# HU_revC.net
KiCad netlist of a schematic drawn in Altium Designer
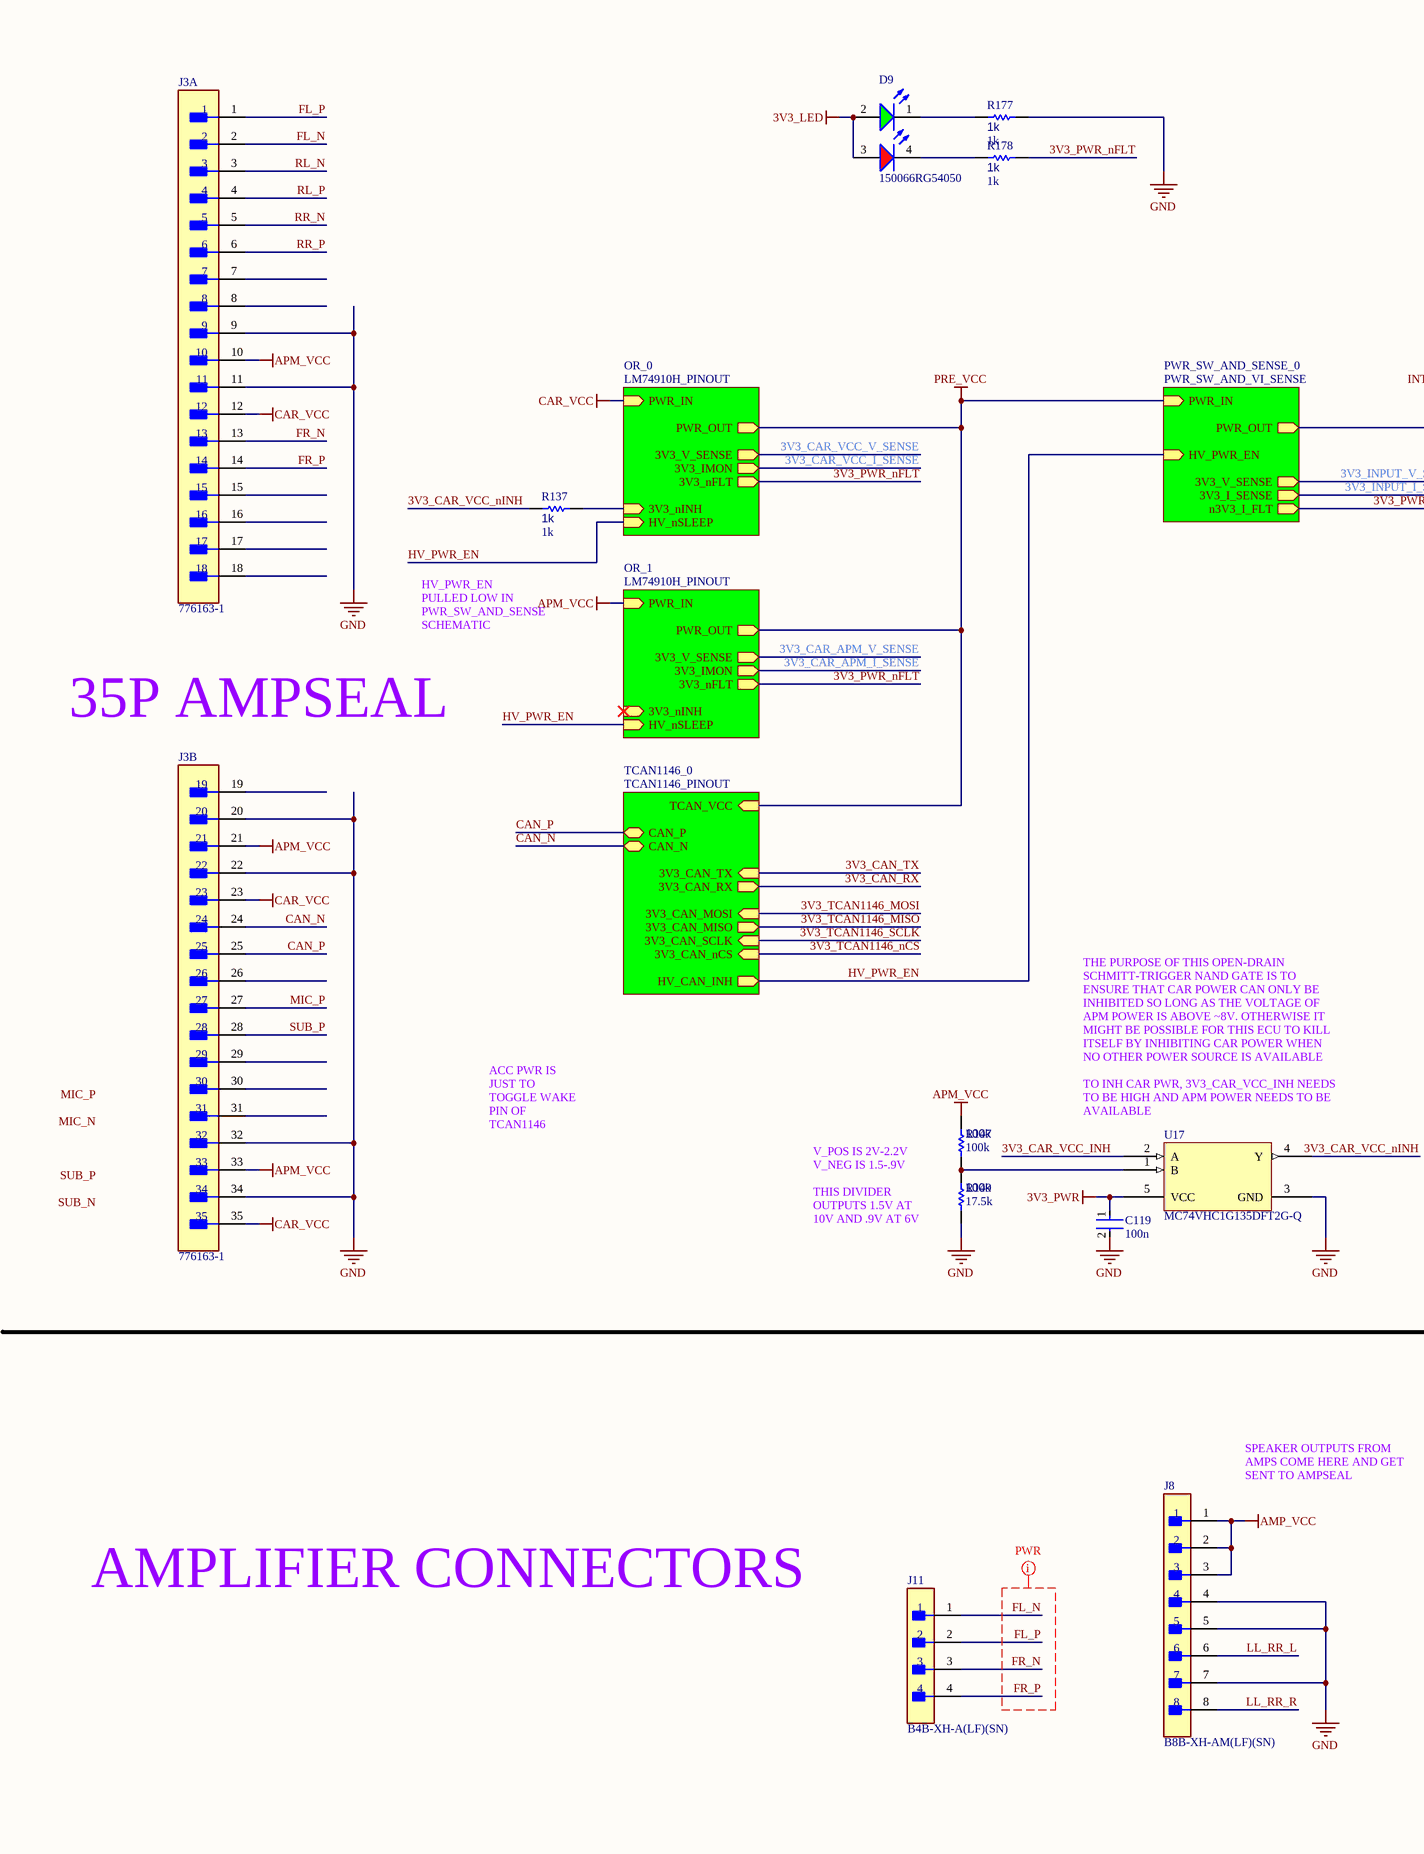
[diagram p0: HU_revC.SchDoc, top left]
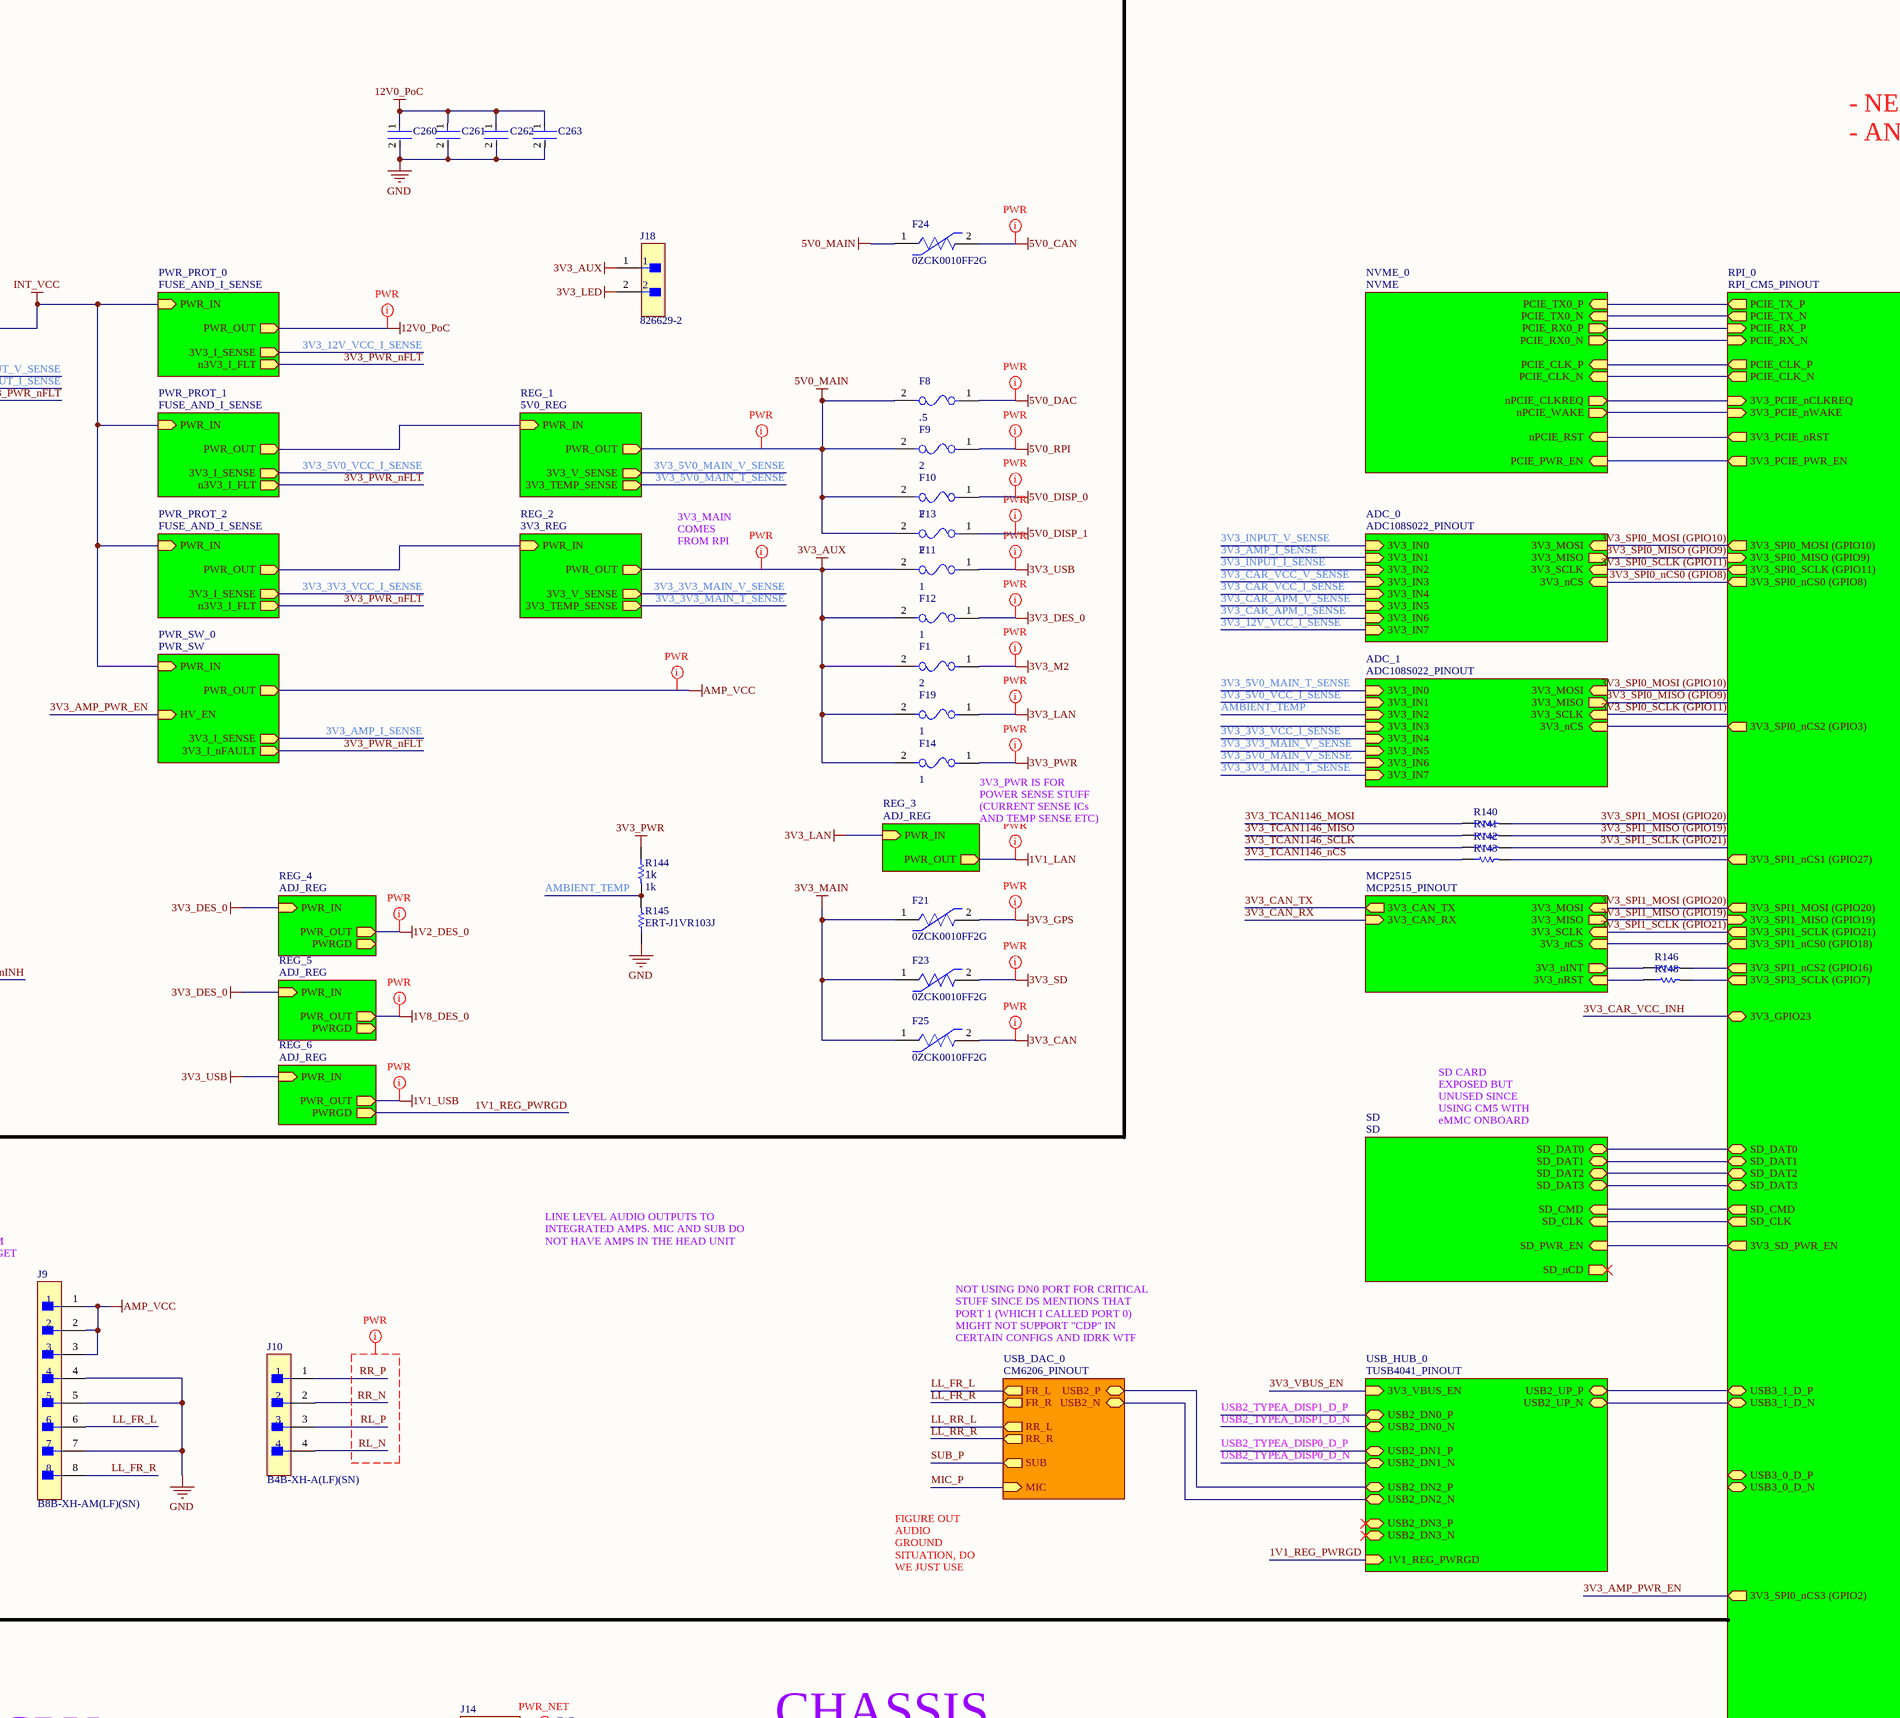
[diagram p1: HU_revC.SchDoc, top middle]
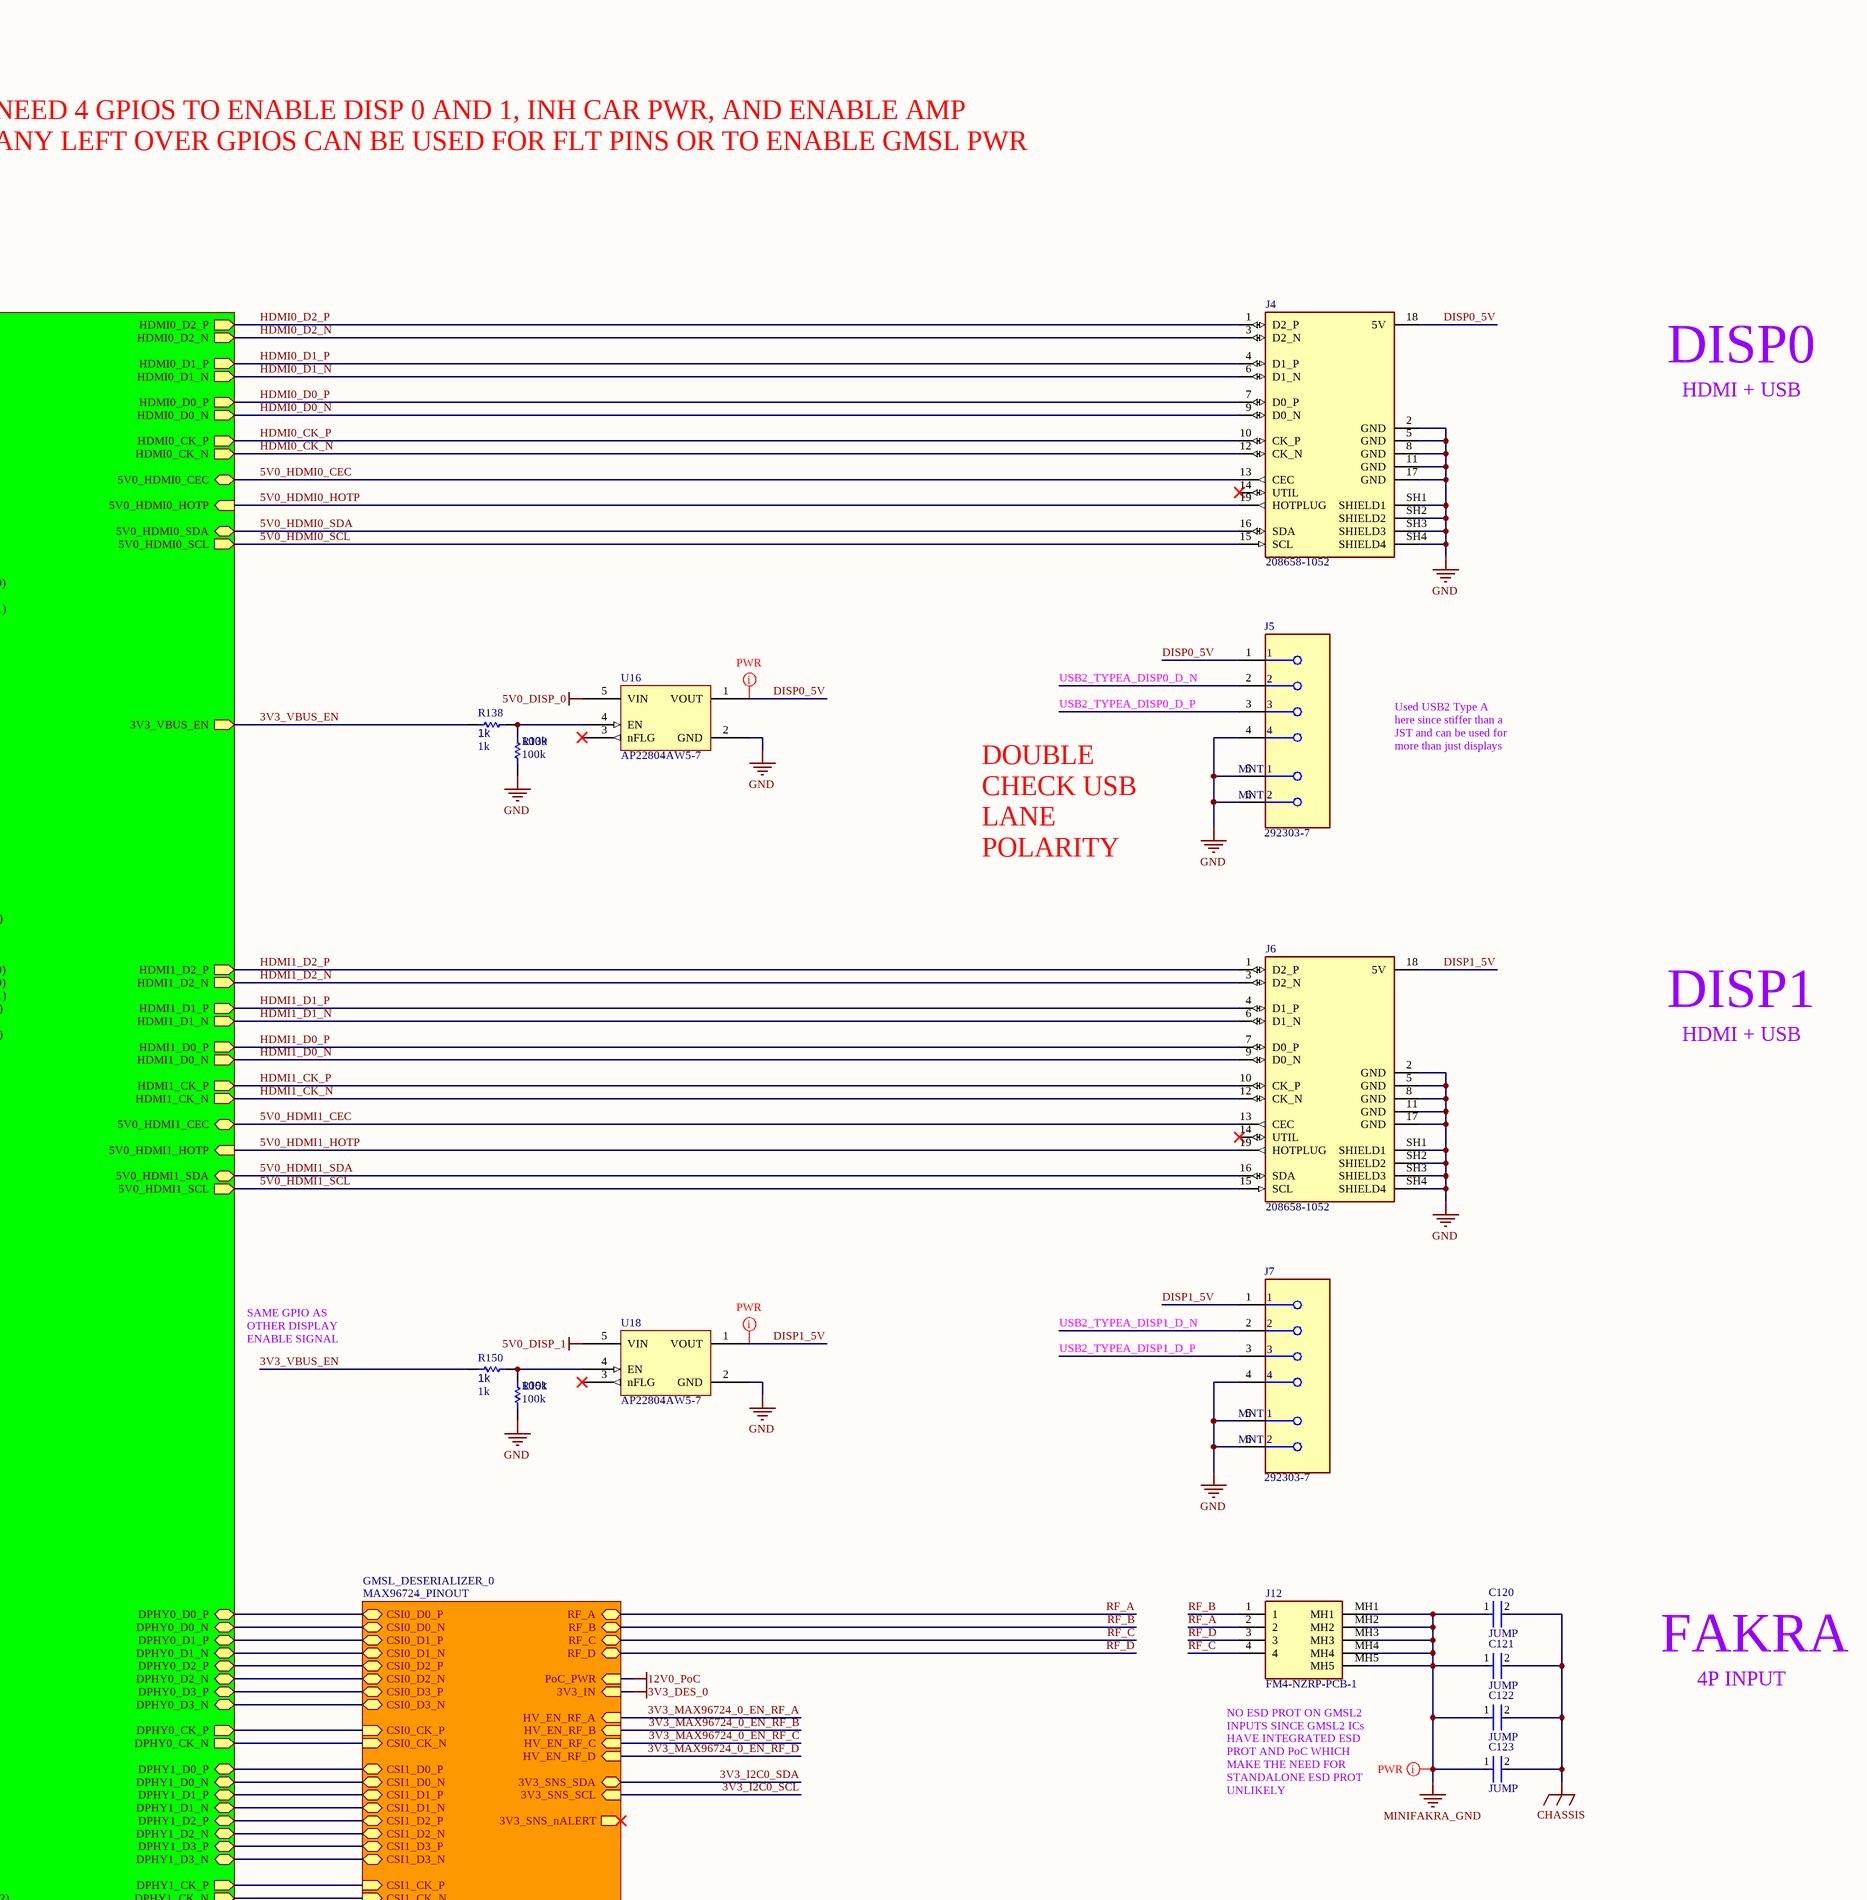
[diagram p2: HU_revC.SchDoc, top right]
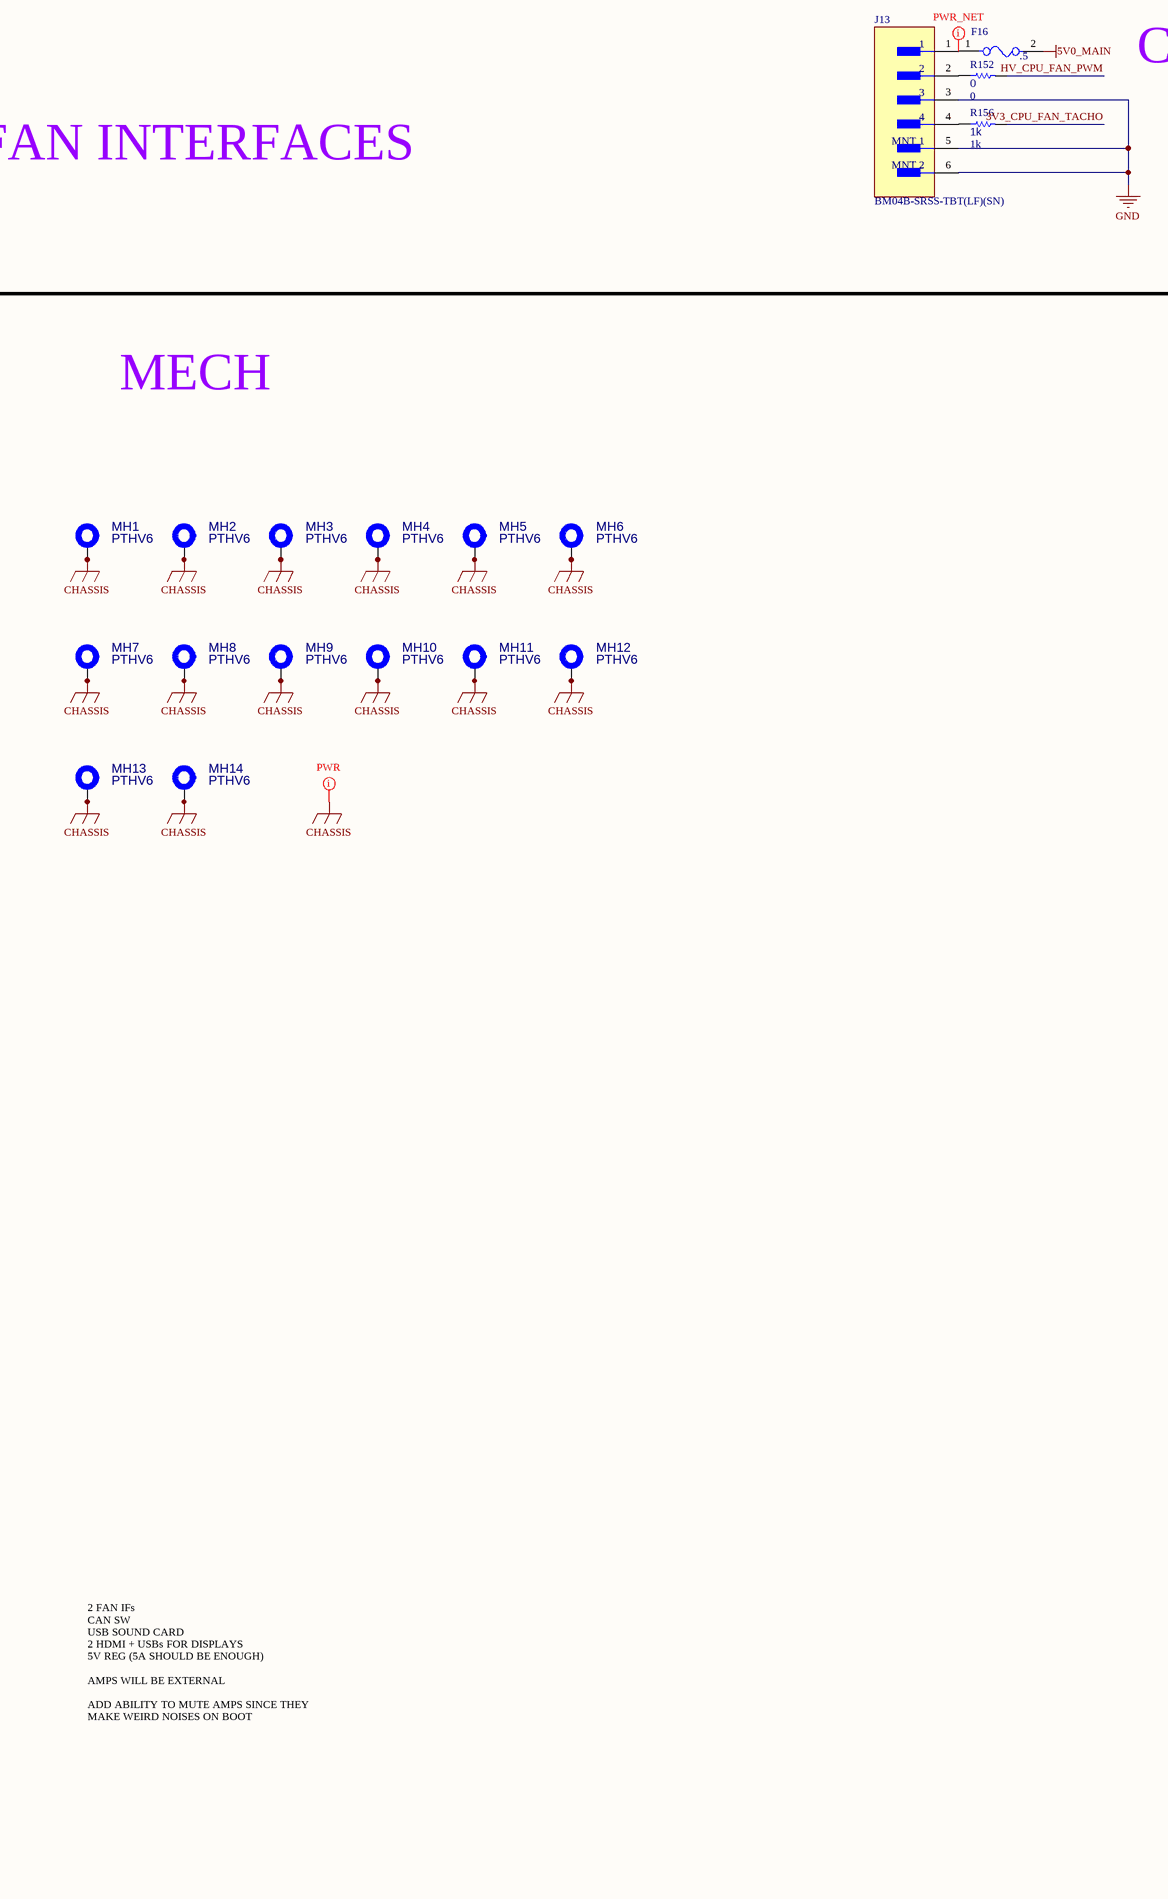
[diagram p3: HU_revC.SchDoc, bottom left]
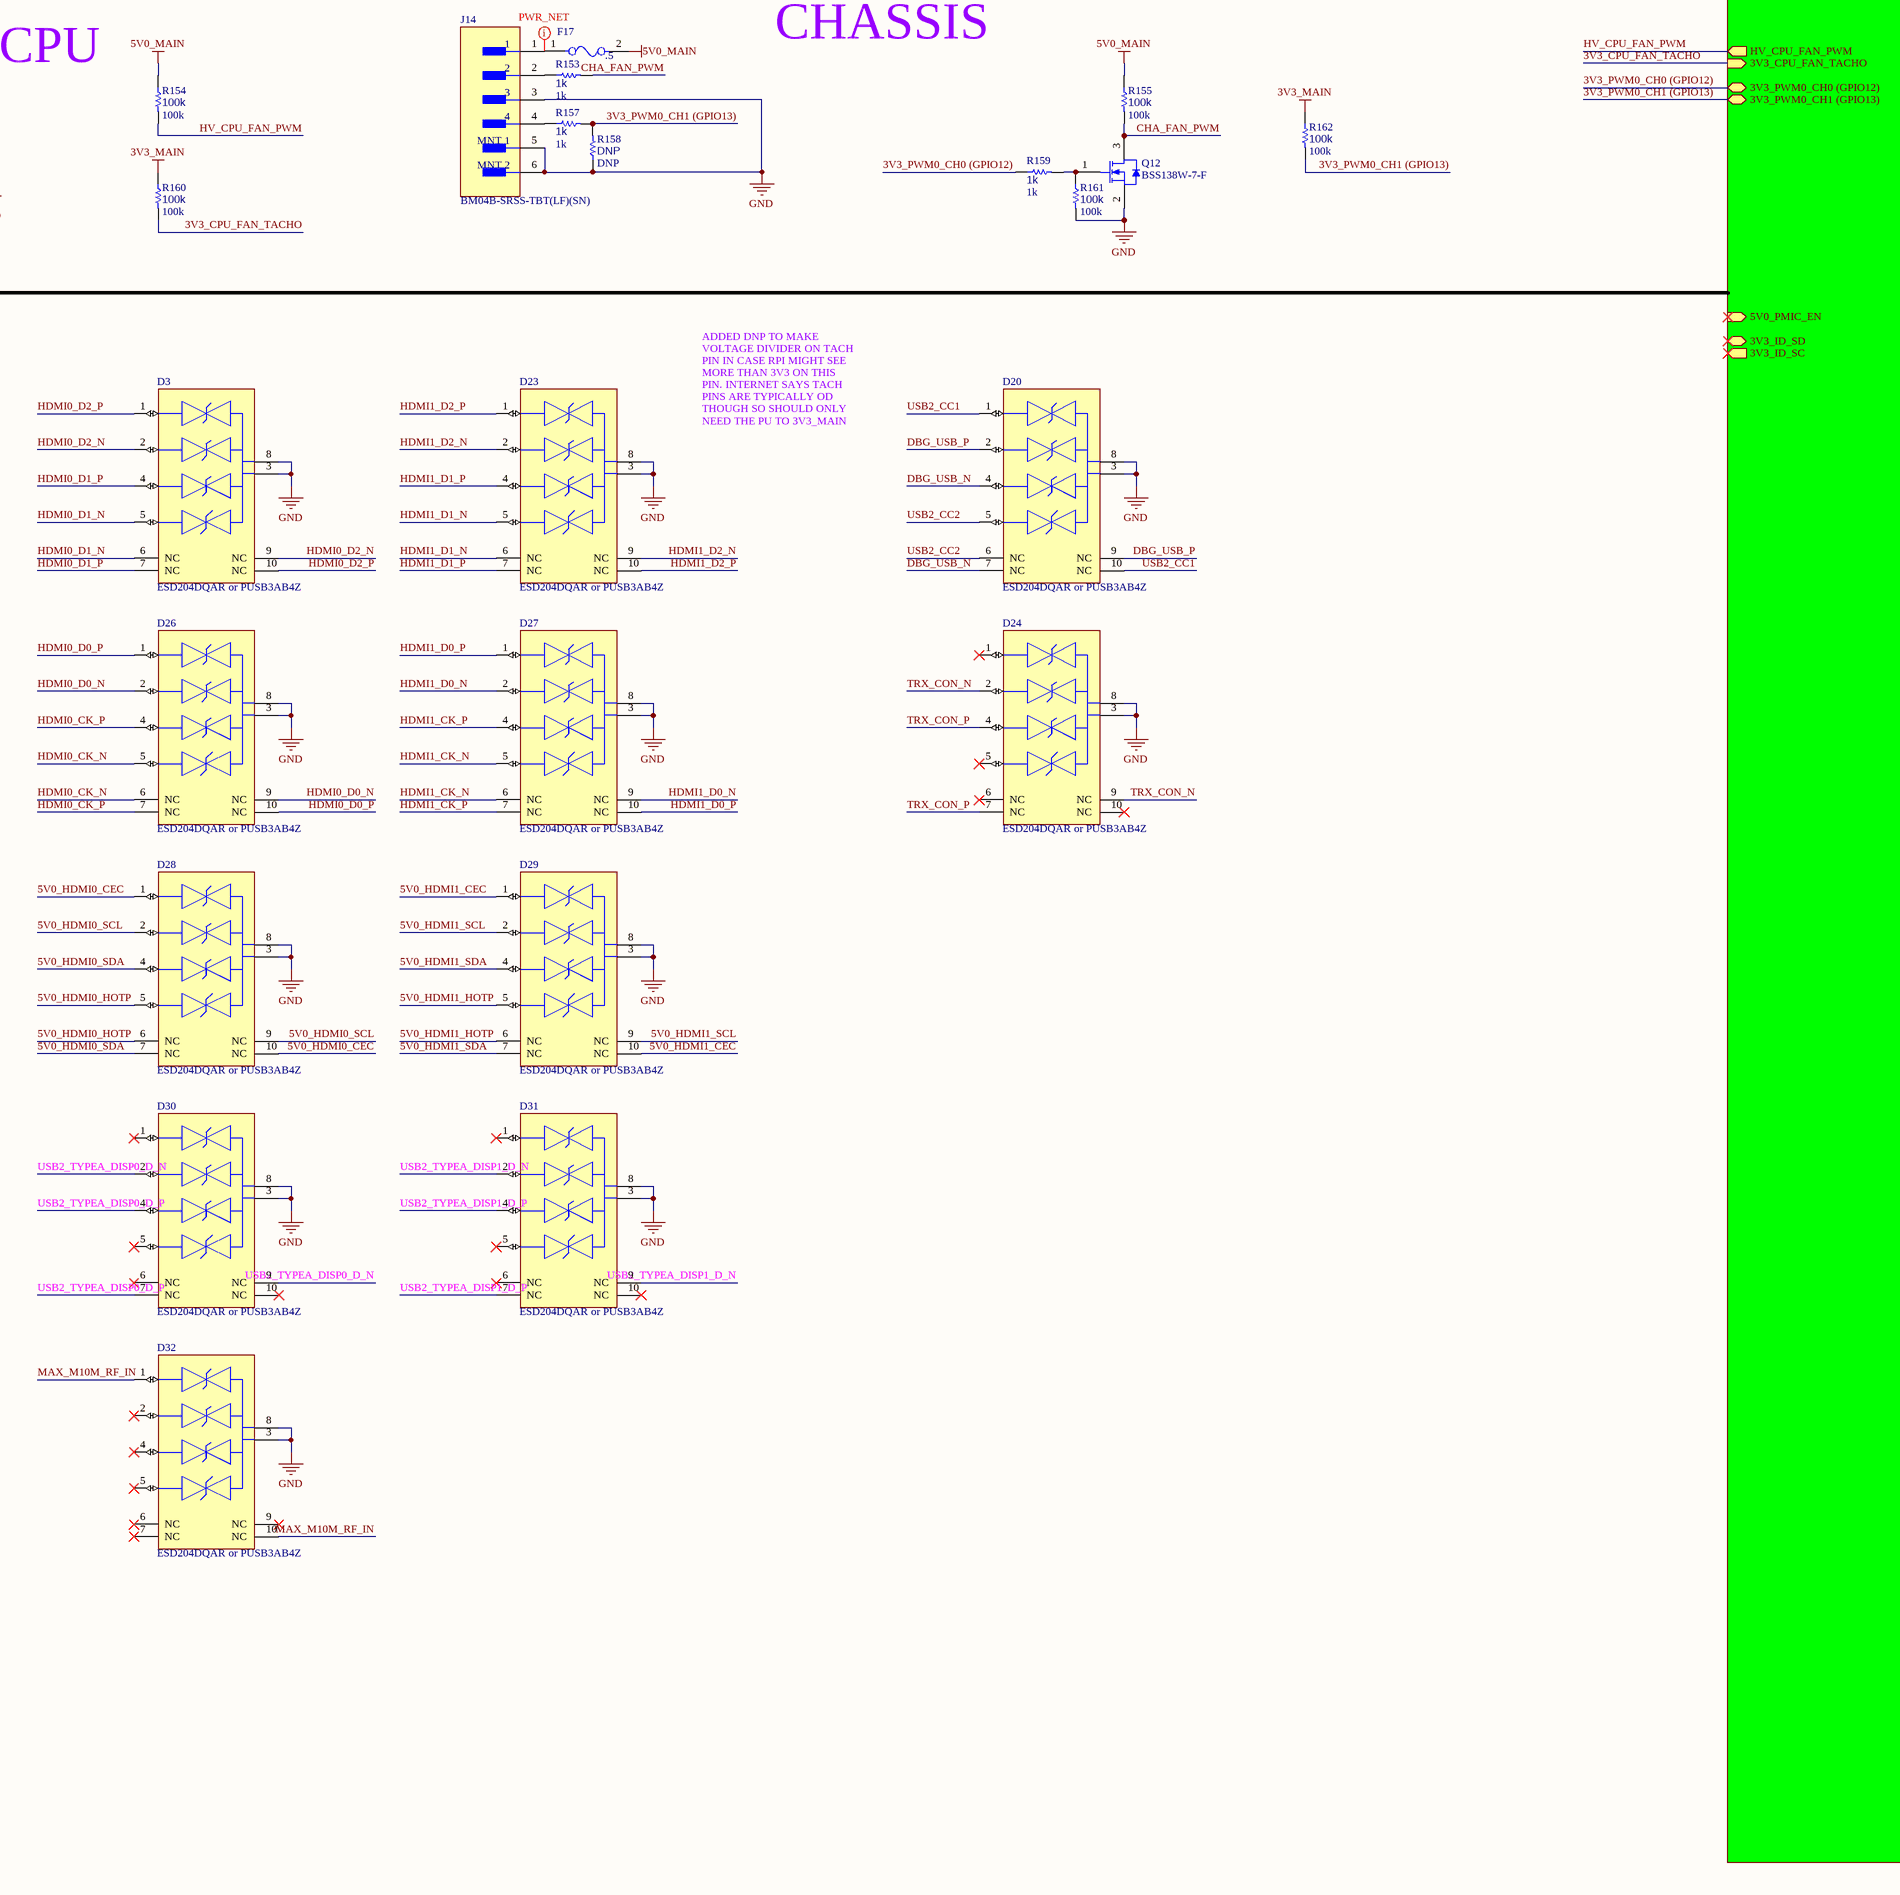
[diagram p4: HU_revC.SchDoc, bottom middle]
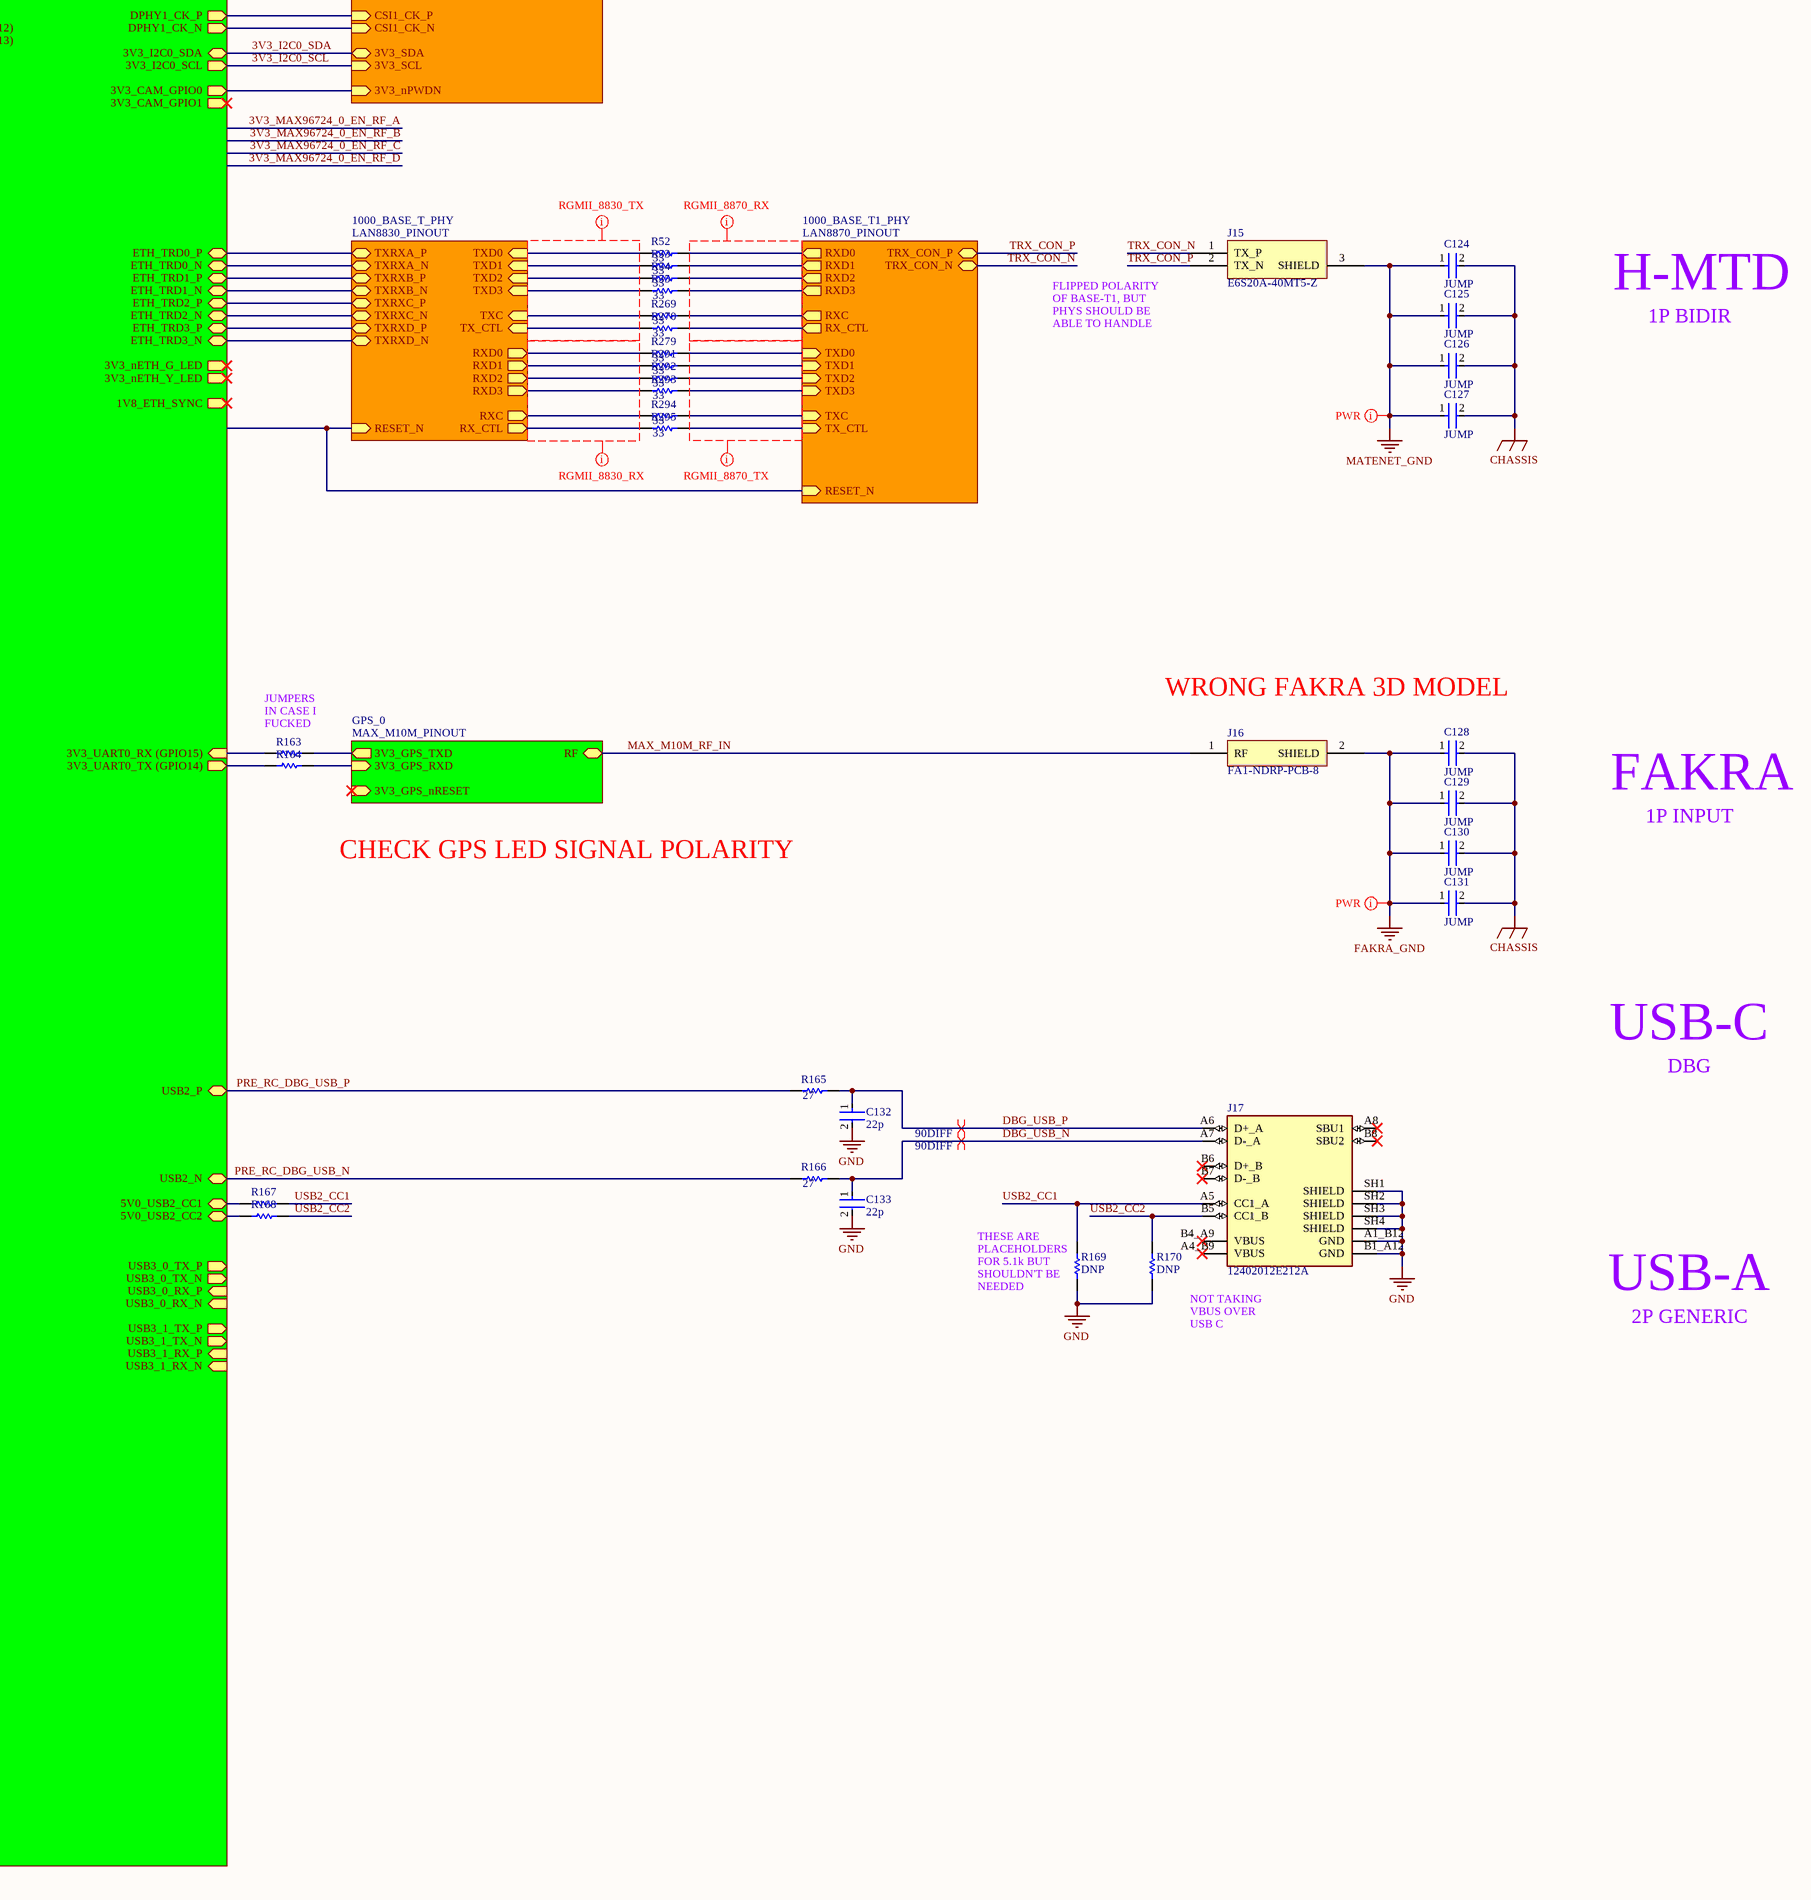
[diagram p5: HU_revC.SchDoc, bottom right]

(export (version "E")
  (design (tool "Eeschema 10.0.6"))
  (components
    (comp (ref "C119")
      (value "100n")
      (footprint "FP-0402-L_1_0_0_05-W_0_5-IPC_A")
      (description "LARGE PADS, 0402 CAP, CHANGE COMMENT TO MATCH REAL P/N")
      (libsource (lib "Space Concordia") (part "b4654b650e69147ec39a6b967a45e02"))
    )
    (comp (ref "C120")
      (value "JUMP")
      (footprint "FP-0402-L_1_0_0_05-W_0_5-IPC_A")
      (description "LARGE PADS, 0402 CAP, CHANGE COMMENT TO MATCH REAL P/N")
      (libsource (lib "Space Concordia") (part "b4654b650e69147ec39a6b967a45e02"))
    )
    (comp (ref "C121")
      (value "JUMP")
      (footprint "FP-0402-L_1_0_0_05-W_0_5-IPC_A")
      (description "LARGE PADS, 0402 CAP, CHANGE COMMENT TO MATCH REAL P/N")
      (libsource (lib "Space Concordia") (part "b4654b650e69147ec39a6b967a45e02"))
    )
    (comp (ref "C122")
      (value "JUMP")
      (footprint "FP-0402-L_1_0_0_05-W_0_5-IPC_A")
      (description "LARGE PADS, 0402 CAP, CHANGE COMMENT TO MATCH REAL P/N")
      (libsource (lib "Space Concordia") (part "b4654b650e69147ec39a6b967a45e02"))
    )
    (comp (ref "C123")
      (value "JUMP")
      (footprint "FP-0402-L_1_0_0_05-W_0_5-IPC_A")
      (description "LARGE PADS, 0402 CAP, CHANGE COMMENT TO MATCH REAL P/N")
      (libsource (lib "Space Concordia") (part "b4654b650e69147ec39a6b967a45e02"))
    )
    (comp (ref "C124")
      (value "JUMP")
      (footprint "FP-0402-L_1_0_0_05-W_0_5-IPC_A")
      (description "LARGE PADS, 0402 CAP, CHANGE COMMENT TO MATCH REAL P/N")
      (libsource (lib "Space Concordia") (part "b4654b650e69147ec39a6b967a45e02"))
    )
    (comp (ref "C125")
      (value "JUMP")
      (footprint "FP-0402-L_1_0_0_05-W_0_5-IPC_A")
      (description "LARGE PADS, 0402 CAP, CHANGE COMMENT TO MATCH REAL P/N")
      (libsource (lib "Space Concordia") (part "b4654b650e69147ec39a6b967a45e02"))
    )
    (comp (ref "C126")
      (value "JUMP")
      (footprint "FP-0402-L_1_0_0_05-W_0_5-IPC_A")
      (description "LARGE PADS, 0402 CAP, CHANGE COMMENT TO MATCH REAL P/N")
      (libsource (lib "Space Concordia") (part "b4654b650e69147ec39a6b967a45e02"))
    )
    (comp (ref "C127")
      (value "JUMP")
      (footprint "FP-0402-L_1_0_0_05-W_0_5-IPC_A")
      (description "LARGE PADS, 0402 CAP, CHANGE COMMENT TO MATCH REAL P/N")
      (libsource (lib "Space Concordia") (part "b4654b650e69147ec39a6b967a45e02"))
    )
    (comp (ref "C128")
      (value "JUMP")
      (footprint "FP-0402-L_1_0_0_05-W_0_5-IPC_A")
      (description "LARGE PADS, 0402 CAP, CHANGE COMMENT TO MATCH REAL P/N")
      (libsource (lib "Space Concordia") (part "b4654b650e69147ec39a6b967a45e02"))
    )
    (comp (ref "C129")
      (value "JUMP")
      (footprint "FP-0402-L_1_0_0_05-W_0_5-IPC_A")
      (description "LARGE PADS, 0402 CAP, CHANGE COMMENT TO MATCH REAL P/N")
      (libsource (lib "Space Concordia") (part "b4654b650e69147ec39a6b967a45e02"))
    )
    (comp (ref "C130")
      (value "JUMP")
      (footprint "FP-0402-L_1_0_0_05-W_0_5-IPC_A")
      (description "LARGE PADS, 0402 CAP, CHANGE COMMENT TO MATCH REAL P/N")
      (libsource (lib "Space Concordia") (part "b4654b650e69147ec39a6b967a45e02"))
    )
    (comp (ref "C131")
      (value "JUMP")
      (footprint "FP-0402-L_1_0_0_05-W_0_5-IPC_A")
      (description "LARGE PADS, 0402 CAP, CHANGE COMMENT TO MATCH REAL P/N")
      (libsource (lib "Space Concordia") (part "b4654b650e69147ec39a6b967a45e02"))
    )
    (comp (ref "C132")
      (value "22p")
      (footprint "FP-0402-L_1_0_0_05-W_0_5-IPC_A")
      (description "LARGE PADS, 0402 CAP, CHANGE COMMENT TO MATCH REAL P/N")
      (libsource (lib "Space Concordia") (part "b4654b650e69147ec39a6b967a45e02"))
    )
    (comp (ref "C133")
      (value "22p")
      (footprint "FP-0402-L_1_0_0_05-W_0_5-IPC_A")
      (description "LARGE PADS, 0402 CAP, CHANGE COMMENT TO MATCH REAL P/N")
      (libsource (lib "Space Concordia") (part "b4654b650e69147ec39a6b967a45e02"))
    )
    (comp (ref "C260")
      (value "GRM32ER61C476KE15L")
      (footprint "FP-GRM32E-0_3-0_2-IPC_C")
      (description "CAP CER 47UF 16V X5R 1210")
      (fields (field (name "VOLTAGE") "16V") (field (name "TOLERANCE") "10%"))
      (libsource (lib "Altium Content Vault") (part "b4654b650e69147ec39a6b967a45e02"))
    )
    (comp (ref "C261")
      (value "GRM32ER61C476KE15L")
      (footprint "FP-GRM32E-0_3-0_2-IPC_C")
      (description "CAP CER 47UF 16V X5R 1210")
      (fields (field (name "VOLTAGE") "16V") (field (name "TOLERANCE") "10%"))
      (libsource (lib "Altium Content Vault") (part "b4654b650e69147ec39a6b967a45e02"))
    )
    (comp (ref "C262")
      (value "GRM32ER61C476KE15L")
      (footprint "FP-GRM32E-0_3-0_2-IPC_C")
      (description "CAP CER 47UF 16V X5R 1210")
      (fields (field (name "VOLTAGE") "16V") (field (name "TOLERANCE") "10%"))
      (libsource (lib "Altium Content Vault") (part "b4654b650e69147ec39a6b967a45e02"))
    )
    (comp (ref "C263")
      (value "GRM32ER61C476KE15L")
      (footprint "FP-GRM32E-0_3-0_2-IPC_C")
      (description "CAP CER 47UF 16V X5R 1210")
      (fields (field (name "VOLTAGE") "16V") (field (name "TOLERANCE") "10%"))
      (libsource (lib "Altium Content Vault") (part "b4654b650e69147ec39a6b967a45e02"))
    )
    (comp (ref "D3")
      (value "ESD204DQAR or PUSB3AB4Z")
      (footprint "FP-DQA0010A-MFG")
      (description "4-CHANNEL LOW-CAPACITANCE SURGE")
      (fields
        (field (name "MANUFACTURER") "Texas Instruments")
        (field (name "OCTOPART") "https://octopart.com/esd204dqar-texas+instruments-89917476")
      )
      (libsource (lib "Altium Content Vault") (part "1465e58c1818c7767b55926832f0bf5"))
    )
    (comp (ref "D9")
      (value "150066RG54050")
      (footprint "WL-SBCD_0606")
      (description "Led, Red/Grn, 180Mcd/230Mcd, 624Nm/525Nm Rohs Compliant: Yes")
      (fields (field (name "SOURCE") "rgled.SchLib"))
      (libsource (lib "Space Concordia") (part "CMP-004-00034-2"))
    )
    (comp (ref "D20")
      (value "ESD204DQAR or PUSB3AB4Z")
      (footprint "FP-DQA0010A-MFG")
      (description "4-CHANNEL LOW-CAPACITANCE SURGE")
      (fields
        (field (name "MANUFACTURER") "Texas Instruments")
        (field (name "OCTOPART") "https://octopart.com/esd204dqar-texas+instruments-89917476")
      )
      (libsource (lib "Altium Content Vault") (part "1465e58c1818c7767b55926832f0bf5"))
    )
    (comp (ref "D23")
      (value "ESD204DQAR or PUSB3AB4Z")
      (footprint "FP-DQA0010A-MFG")
      (description "4-CHANNEL LOW-CAPACITANCE SURGE")
      (fields
        (field (name "MANUFACTURER") "Texas Instruments")
        (field (name "OCTOPART") "https://octopart.com/esd204dqar-texas+instruments-89917476")
      )
      (libsource (lib "Altium Content Vault") (part "1465e58c1818c7767b55926832f0bf5"))
    )
    (comp (ref "D24")
      (value "ESD204DQAR or PUSB3AB4Z")
      (footprint "FP-DQA0010A-MFG")
      (description "4-CHANNEL LOW-CAPACITANCE SURGE")
      (fields
        (field (name "MANUFACTURER") "Texas Instruments")
        (field (name "OCTOPART") "https://octopart.com/esd204dqar-texas+instruments-89917476")
      )
      (libsource (lib "Altium Content Vault") (part "1465e58c1818c7767b55926832f0bf5"))
    )
    (comp (ref "D26")
      (value "ESD204DQAR or PUSB3AB4Z")
      (footprint "FP-DQA0010A-MFG")
      (description "4-CHANNEL LOW-CAPACITANCE SURGE")
      (fields
        (field (name "MANUFACTURER") "Texas Instruments")
        (field (name "OCTOPART") "https://octopart.com/esd204dqar-texas+instruments-89917476")
      )
      (libsource (lib "Altium Content Vault") (part "1465e58c1818c7767b55926832f0bf5"))
    )
    (comp (ref "D27")
      (value "ESD204DQAR or PUSB3AB4Z")
      (footprint "FP-DQA0010A-MFG")
      (description "4-CHANNEL LOW-CAPACITANCE SURGE")
      (fields
        (field (name "MANUFACTURER") "Texas Instruments")
        (field (name "OCTOPART") "https://octopart.com/esd204dqar-texas+instruments-89917476")
      )
      (libsource (lib "Altium Content Vault") (part "1465e58c1818c7767b55926832f0bf5"))
    )
    (comp (ref "D28")
      (value "ESD204DQAR or PUSB3AB4Z")
      (footprint "FP-DQA0010A-MFG")
      (description "4-CHANNEL LOW-CAPACITANCE SURGE")
      (fields
        (field (name "MANUFACTURER") "Texas Instruments")
        (field (name "OCTOPART") "https://octopart.com/esd204dqar-texas+instruments-89917476")
      )
      (libsource (lib "Altium Content Vault") (part "1465e58c1818c7767b55926832f0bf5"))
    )
    (comp (ref "D29")
      (value "ESD204DQAR or PUSB3AB4Z")
      (footprint "FP-DQA0010A-MFG")
      (description "4-CHANNEL LOW-CAPACITANCE SURGE")
      (fields
        (field (name "MANUFACTURER") "Texas Instruments")
        (field (name "OCTOPART") "https://octopart.com/esd204dqar-texas+instruments-89917476")
      )
      (libsource (lib "Altium Content Vault") (part "1465e58c1818c7767b55926832f0bf5"))
    )
    (comp (ref "D30")
      (value "ESD204DQAR or PUSB3AB4Z")
      (footprint "FP-DQA0010A-MFG")
      (description "4-CHANNEL LOW-CAPACITANCE SURGE")
      (fields
        (field (name "MANUFACTURER") "Texas Instruments")
        (field (name "OCTOPART") "https://octopart.com/esd204dqar-texas+instruments-89917476")
      )
      (libsource (lib "Altium Content Vault") (part "1465e58c1818c7767b55926832f0bf5"))
    )
    (comp (ref "D31")
      (value "ESD204DQAR or PUSB3AB4Z")
      (footprint "FP-DQA0010A-MFG")
      (description "4-CHANNEL LOW-CAPACITANCE SURGE")
      (fields
        (field (name "MANUFACTURER") "Texas Instruments")
        (field (name "OCTOPART") "https://octopart.com/esd204dqar-texas+instruments-89917476")
      )
      (libsource (lib "Altium Content Vault") (part "1465e58c1818c7767b55926832f0bf5"))
    )
    (comp (ref "D32")
      (value "ESD204DQAR or PUSB3AB4Z")
      (footprint "FP-DQA0010A-MFG")
      (description "4-CHANNEL LOW-CAPACITANCE SURGE")
      (fields
        (field (name "MANUFACTURER") "Texas Instruments")
        (field (name "OCTOPART") "https://octopart.com/esd204dqar-texas+instruments-89917476")
      )
      (libsource (lib "Altium Content Vault") (part "1465e58c1818c7767b55926832f0bf5"))
    )
    (comp (ref "F1")
      (value "2")
      (footprint "FP-0685T-MFG")
      (description "FUSE BOARD MNT 5A 63VAC/VDC 1206")
      (libsource (lib "Altium Content Vault") (part "5bcf9b9f640e542cf0359d10258e979"))
    )
    (comp (ref "F8")
      (value ".5")
      (footprint "FP-0685T-MFG")
      (description "FUSE BOARD MNT 5A 63VAC/VDC 1206")
      (libsource (lib "Altium Content Vault") (part "5bcf9b9f640e542cf0359d10258e979"))
    )
    (comp (ref "F9")
      (value "2")
      (footprint "FP-0685T-MFG")
      (description "FUSE BOARD MNT 5A 63VAC/VDC 1206")
      (libsource (lib "Altium Content Vault") (part "5bcf9b9f640e542cf0359d10258e979"))
    )
    (comp (ref "F10")
      (value "2")
      (footprint "FP-0685T-MFG")
      (description "FUSE BOARD MNT 5A 63VAC/VDC 1206")
      (libsource (lib "Altium Content Vault") (part "5bcf9b9f640e542cf0359d10258e979"))
    )
    (comp (ref "F11")
      (value "1")
      (footprint "FP-0685T-MFG")
      (description "FUSE BOARD MNT 5A 63VAC/VDC 1206")
      (libsource (lib "Altium Content Vault") (part "5bcf9b9f640e542cf0359d10258e979"))
    )
    (comp (ref "F12")
      (value "1")
      (footprint "FP-0685T-MFG")
      (description "FUSE BOARD MNT 5A 63VAC/VDC 1206")
      (libsource (lib "Altium Content Vault") (part "5bcf9b9f640e542cf0359d10258e979"))
    )
    (comp (ref "F13")
      (value "2")
      (footprint "FP-0685T-MFG")
      (description "FUSE BOARD MNT 5A 63VAC/VDC 1206")
      (libsource (lib "Altium Content Vault") (part "5bcf9b9f640e542cf0359d10258e979"))
    )
    (comp (ref "F14")
      (value "1")
      (footprint "FP-0685T-MFG")
      (description "FUSE BOARD MNT 5A 63VAC/VDC 1206")
      (libsource (lib "Altium Content Vault") (part "5bcf9b9f640e542cf0359d10258e979"))
    )
    (comp (ref "F16")
      (value ".5")
      (footprint "FP-0685T-MFG")
      (description "FUSE BOARD MNT 5A 63VAC/VDC 1206")
      (libsource (lib "Altium Content Vault") (part "5bcf9b9f640e542cf0359d10258e979"))
    )
    (comp (ref "F17")
      (value ".5")
      (footprint "FP-0685T-MFG")
      (description "FUSE BOARD MNT 5A 63VAC/VDC 1206")
      (libsource (lib "Altium Content Vault") (part "5bcf9b9f640e542cf0359d10258e979"))
    )
    (comp (ref "F19")
      (value "1")
      (footprint "FP-0685T-MFG")
      (description "FUSE BOARD MNT 5A 63VAC/VDC 1206")
      (libsource (lib "Altium Content Vault") (part "5bcf9b9f640e542cf0359d10258e979"))
    )
    (comp (ref "F21")
      (value "0ZCK0010FF2G")
      (footprint "FP-0ZCK0010FF2G-MFG")
      (description "PTC RESET FUSE 15V 100MA 0805")
      (libsource (lib "Altium Content Vault") (part "fc31388045fc42ab786d6d00b506e9f"))
    )
    (comp (ref "F23")
      (value "0ZCK0010FF2G")
      (footprint "FP-0ZCK0010FF2G-MFG")
      (description "PTC RESET FUSE 15V 100MA 0805")
      (libsource (lib "Altium Content Vault") (part "fc31388045fc42ab786d6d00b506e9f"))
    )
    (comp (ref "F24")
      (value "0ZCK0010FF2G")
      (footprint "FP-0ZCK0010FF2G-MFG")
      (description "PTC RESET FUSE 15V 100MA 0805")
      (libsource (lib "Altium Content Vault") (part "fc31388045fc42ab786d6d00b506e9f"))
    )
    (comp (ref "F25")
      (value "0ZCK0010FF2G")
      (footprint "FP-0ZCK0010FF2G-MFG")
      (description "PTC RESET FUSE 15V 100MA 0805")
      (libsource (lib "Altium Content Vault") (part "fc31388045fc42ab786d6d00b506e9f"))
    )
    (comp (ref "J3")
      (value "776163-1")
      (footprint "FP-776163-1-MFG")
      (description "CONN HEADER R/A 35POS 4MM")
      (libsource (lib "Altium Content Vault") (part "519b18991870a11d3ebcd8ad3c0113e"))
    )
    (comp (ref "J4")
      (value "208658-1052")
      (footprint "208658-1052-Footprint-1")
      (description "HDMI CONNECTOR, RCPT, 19POS, SMT; Available until stocks are exhausted Alternative available")
      (libsource (lib "Space Concordia") (part "208658-1052"))
    )
    (comp (ref "J5")
      (value "292303-7")
      (footprint "FP-292303-7-MFG")
      (description "CONN RCPT USB2.0 TYPEA 4P SMD RA")
      (fields
        (field (name "OCTOPART") "https://octopart.com/292303-7-te+connectivity-42840369")
        (field (name "MANUFACTURER") "TE Connectivity")
      )
      (libsource (lib "Altium Content Vault") (part "79e6714efa0bb2f851c24b2688127c9"))
    )
    (comp (ref "J6")
      (value "208658-1052")
      (footprint "208658-1052-Footprint-1")
      (description "HDMI CONNECTOR, RCPT, 19POS, SMT; Available until stocks are exhausted Alternative available")
      (libsource (lib "Space Concordia") (part "208658-1052"))
    )
    (comp (ref "J7")
      (value "292303-7")
      (footprint "FP-292303-7-MFG")
      (description "CONN RCPT USB2.0 TYPEA 4P SMD RA")
      (fields
        (field (name "OCTOPART") "https://octopart.com/292303-7-te+connectivity-42840369")
        (field (name "MANUFACTURER") "TE Connectivity")
      )
      (libsource (lib "Altium Content Vault") (part "79e6714efa0bb2f851c24b2688127c9"))
    )
    (comp (ref "J8")
      (value "B8B-XH-AM(LF)(SN)")
      (footprint "FP-B8B-XH-AM_LF_SN-MFG")
      (description "CONN HEADER VERT 8POS 2.5MM")
      (libsource (lib "Altium Content Vault") (part "99ec2b232beb5d2356d4d77f6a047f0"))
    )
    (comp (ref "J9")
      (value "B8B-XH-AM(LF)(SN)")
      (footprint "FP-B8B-XH-AM_LF_SN-MFG")
      (description "CONN HEADER VERT 8POS 2.5MM")
      (libsource (lib "Altium Content Vault") (part "99ec2b232beb5d2356d4d77f6a047f0"))
    )
    (comp (ref "J10")
      (value "B4B-XH-A(LF)(SN)")
      (footprint "FP-B4B-XH-A_LF_SN-MFG")
      (description "CONN HEADER VERT 4POS 2.5MM")
      (libsource (lib "Altium Content Vault") (part "299a8cea1bdcbc3624fe62c390fa72c"))
    )
    (comp (ref "J11")
      (value "B4B-XH-A(LF)(SN)")
      (footprint "FP-B4B-XH-A_LF_SN-MFG")
      (description "CONN HEADER VERT 4POS 2.5MM")
      (libsource (lib "Altium Content Vault") (part "299a8cea1bdcbc3624fe62c390fa72c"))
    )
    (comp (ref "J12")
      (value "FM4-NZRP-PCB-1")
      (footprint "FM4-NZRP-PCB-1-Footprint-1")
      (description "Connector RF Mini-FAKRA Plug 9GHz 50Ohm Solder Right Angle Through Hole")
      (libsource (lib "Space Concordia") (part "CMP-002-00085-1"))
    )
    (comp (ref "J13")
      (value "BM04B-SRSS-TBT(LF)(SN)")
      (footprint "FP-BM04B-SRSS-TBT_LF_SN-MFG")
      (description "CONN HEADER SMD 4POS 1MM")
      (libsource (lib "Altium Content Vault") (part "8e3688c4b118bffc0dd9b7401e414ba"))
    )
    (comp (ref "J14")
      (value "BM04B-SRSS-TBT(LF)(SN)")
      (footprint "FP-BM04B-SRSS-TBT_LF_SN-MFG")
      (description "CONN HEADER SMD 4POS 1MM")
      (libsource (lib "Altium Content Vault") (part "8e3688c4b118bffc0dd9b7401e414ba"))
    )
    (comp (ref "J15")
      (value "E6S20A-40MT5-Z")
      (footprint "E6S20A-40MT5-Z-Footprint-1")
      (description "RF Connector, 2 Contact(s), Male, Panel Mount, Board And Panel Mount, Solder Terminal, Plug")
      (libsource (lib "Space Concordia") (part "E6S20A-40MT5-Z"))
    )
    (comp (ref "J16")
      (value "FA1-NDRP-PCB-8")
      (footprint "FA1-NDRP-PCB-8-Footprint-1")
      (description "RF F Connector, Male, Board Mount, Solder Terminal, Plug")
      (libsource (lib "Space Concordia") (part "FA1-NDRP-PCB-8"))
    )
    (comp (ref "J17")
      (value "12402012E212A")
      (footprint "12402012E212A-Footprint-1")
      (description "USB Connector, USB Type C, USB 2.0, Receptacle, 24 Ways, Surface Mount, Through Hole Mount")
      (libsource (lib "Space Concordia") (part "12402012E212A"))
    )
    (comp (ref "J18")
      (value "826629-2")
      (footprint "FP-826629-2-MFG")
      (description "CONN HEADER VERT 2POS 2.54MM")
      (libsource (lib "Altium Content Vault") (part "3bc925449376181038e59eaffc5286c"))
    )
    (comp (ref "MH1")
      (value "PTHV6")
      (footprint "PTHV6 M2")
      (libsource (lib "Space Concordia") (part "PTHV6"))
    )
    (comp (ref "MH2")
      (value "PTHV6")
      (footprint "PTHV6 M2")
      (libsource (lib "Space Concordia") (part "PTHV6"))
    )
    (comp (ref "MH3")
      (value "PTHV6")
      (footprint "PTHV6 M2")
      (libsource (lib "Space Concordia") (part "PTHV6"))
    )
    (comp (ref "MH4")
      (value "PTHV6")
      (footprint "PTHV6 M2")
      (libsource (lib "Space Concordia") (part "PTHV6"))
    )
    (comp (ref "MH5")
      (value "PTHV6")
      (footprint "PTHV6 M2")
      (libsource (lib "Space Concordia") (part "PTHV6"))
    )
    (comp (ref "MH6")
      (value "PTHV6")
      (footprint "PTHV6 M2")
      (libsource (lib "Space Concordia") (part "PTHV6"))
    )
    (comp (ref "MH7")
      (value "PTHV6")
      (footprint "PTHV6 M2")
      (libsource (lib "Space Concordia") (part "PTHV6"))
    )
    (comp (ref "MH8")
      (value "PTHV6")
      (footprint "PTHV6 M2")
      (libsource (lib "Space Concordia") (part "PTHV6"))
    )
    (comp (ref "MH9")
      (value "PTHV6")
      (footprint "PTHV6 M2")
      (libsource (lib "Space Concordia") (part "PTHV6"))
    )
    (comp (ref "MH10")
      (value "PTHV6")
      (footprint "PTHV6 M2")
      (libsource (lib "Space Concordia") (part "PTHV6"))
    )
    (comp (ref "MH11")
      (value "PTHV6")
      (footprint "PTHV6 M2")
      (libsource (lib "Space Concordia") (part "PTHV6"))
    )
    (comp (ref "MH12")
      (value "PTHV6")
      (footprint "PTHV6 M2")
      (libsource (lib "Space Concordia") (part "PTHV6"))
    )
    (comp (ref "MH13")
      (value "PTHV6")
      (footprint "PTHV6 M2")
      (libsource (lib "Space Concordia") (part "PTHV6"))
    )
    (comp (ref "MH14")
      (value "PTHV6")
      (footprint "PTHV6 M2")
      (libsource (lib "Space Concordia") (part "PTHV6"))
    )
    (comp (ref "Q12")
      (value "BSS138W-7-F")
      (footprint "DIOD-SOT323-3_V")
      (fields (field (name "MANUFACTURER") "DiodesIncorporated"))
      (libsource (lib "Altium Content Vault") (part "NEMOS-GSD-3"))
    )
    (comp (ref "R52")
      (value "33")
      (footprint "R0603B")
      (description "Resistor")
      (libsource (lib "Space Concordia") (part "Resistor"))
    )
    (comp (ref "R53")
      (value "33")
      (footprint "R0603B")
      (description "Resistor")
      (libsource (lib "Space Concordia") (part "Resistor"))
    )
    (comp (ref "R54")
      (value "33")
      (footprint "R0603B")
      (description "Resistor")
      (libsource (lib "Space Concordia") (part "Resistor"))
    )
    (comp (ref "R55")
      (value "33")
      (footprint "R0603B")
      (description "Resistor")
      (libsource (lib "Space Concordia") (part "Resistor"))
    )
    (comp (ref "R137")
      (value "1k")
      (footprint "R0603B")
      (description "Resistor")
      (fields (field (name "ALTIUM_VALUE") "1k"))
      (libsource (lib "Space Concordia") (part "Resistor"))
    )
    (comp (ref "R138")
      (value "1k")
      (footprint "R0603B")
      (description "Resistor")
      (fields (field (name "ALTIUM_VALUE") "1k"))
      (libsource (lib "Space Concordia") (part "Resistor"))
    )
    (comp (ref "R139")
      (value "100k")
      (footprint "R0603B")
      (description "Resistor")
      (fields (field (name "ALTIUM_VALUE") "100k"))
      (libsource (lib "Space Concordia") (part "Resistor"))
    )
    (comp (ref "R140")
      (value "0402 JUMPER")
      (footprint "RESC1005X40X25ML05T05")
      (description "READ THE NAME")
      (libsource (lib "Space Concordia") (part "CMP-009-00206-2"))
    )
    (comp (ref "R141")
      (value "0402 JUMPER")
      (footprint "RESC1005X40X25ML05T05")
      (description "READ THE NAME")
      (libsource (lib "Space Concordia") (part "CMP-009-00206-2"))
    )
    (comp (ref "R142")
      (value "0402 JUMPER")
      (footprint "RESC1005X40X25ML05T05")
      (description "READ THE NAME")
      (libsource (lib "Space Concordia") (part "CMP-009-00206-2"))
    )
    (comp (ref "R143")
      (value "0402 JUMPER")
      (footprint "RESC1005X40X25ML05T05")
      (description "READ THE NAME")
      (libsource (lib "Space Concordia") (part "CMP-009-00206-2"))
    )
    (comp (ref "R144")
      (value "1k")
      (footprint "R0603B")
      (description "Resistor")
      (fields (field (name "ALTIUM_VALUE") "1k"))
      (libsource (lib "Space Concordia") (part "Resistor"))
    )
    (comp (ref "R145")
      (value "ERT-J1VR103J")
      (footprint "RESC1608X90X30ML15T20")
      (fields (field (name "MANUFACTURER") "Panasonic"))
      (libsource (lib "Altium Content Vault") (part "RES"))
    )
    (comp (ref "R146")
      (value "0402 JUMPER")
      (footprint "RESC1005X40X25ML05T05")
      (description "READ THE NAME")
      (libsource (lib "Space Concordia") (part "CMP-009-00206-2"))
    )
    (comp (ref "R147")
      (value "100k")
      (footprint "R0603B")
      (description "Resistor")
      (fields (field (name "ALTIUM_VALUE") "100k"))
      (libsource (lib "Space Concordia") (part "Resistor"))
    )
    (comp (ref "R148")
      (value "0402 JUMPER")
      (footprint "RESC1005X40X25ML05T05")
      (description "READ THE NAME")
      (libsource (lib "Space Concordia") (part "CMP-009-00206-2"))
    )
    (comp (ref "R149")
      (value "17.5k")
      (footprint "R0603B")
      (description "Resistor")
      (fields (field (name "ALTIUM_VALUE") "100k"))
      (libsource (lib "Space Concordia") (part "Resistor"))
    )
    (comp (ref "R150")
      (value "1k")
      (footprint "R0603B")
      (description "Resistor")
      (fields (field (name "ALTIUM_VALUE") "1k"))
      (libsource (lib "Space Concordia") (part "Resistor"))
    )
    (comp (ref "R151")
      (value "100k")
      (footprint "R0603B")
      (description "Resistor")
      (fields (field (name "ALTIUM_VALUE") "100k"))
      (libsource (lib "Space Concordia") (part "Resistor"))
    )
    (comp (ref "R152")
      (value "0")
      (footprint "R0603B")
      (description "Resistor")
      (fields (field (name "ALTIUM_VALUE") "0"))
      (libsource (lib "Space Concordia") (part "Resistor"))
    )
    (comp (ref "R153")
      (value "1k")
      (footprint "R0603B")
      (description "Resistor")
      (fields (field (name "ALTIUM_VALUE") "1k"))
      (libsource (lib "Space Concordia") (part "Resistor"))
    )
    (comp (ref "R154")
      (value "100k")
      (footprint "R0603B")
      (description "Resistor")
      (fields (field (name "ALTIUM_VALUE") "100k"))
      (libsource (lib "Space Concordia") (part "Resistor"))
    )
    (comp (ref "R155")
      (value "100k")
      (footprint "R0603B")
      (description "Resistor")
      (fields (field (name "ALTIUM_VALUE") "100k"))
      (libsource (lib "Space Concordia") (part "Resistor"))
    )
    (comp (ref "R156")
      (value "1k")
      (footprint "R0603B")
      (description "Resistor")
      (fields (field (name "ALTIUM_VALUE") "1k"))
      (libsource (lib "Space Concordia") (part "Resistor"))
    )
    (comp (ref "R157")
      (value "1k")
      (footprint "R0603B")
      (description "Resistor")
      (fields (field (name "ALTIUM_VALUE") "1k"))
      (libsource (lib "Space Concordia") (part "Resistor"))
    )
    (comp (ref "R158")
      (value "DNP")
      (footprint "R0603B")
      (description "Resistor")
      (fields (field (name "ALTIUM_VALUE") "DNP"))
      (libsource (lib "Space Concordia") (part "Resistor"))
    )
    (comp (ref "R159")
      (value "1k")
      (footprint "R0603B")
      (description "Resistor")
      (fields (field (name "ALTIUM_VALUE") "1k"))
      (libsource (lib "Space Concordia") (part "Resistor"))
    )
    (comp (ref "R160")
      (value "100k")
      (footprint "R0603B")
      (description "Resistor")
      (fields (field (name "ALTIUM_VALUE") "100k"))
      (libsource (lib "Space Concordia") (part "Resistor"))
    )
    (comp (ref "R161")
      (value "100k")
      (footprint "R0603B")
      (description "Resistor")
      (fields (field (name "ALTIUM_VALUE") "100k"))
      (libsource (lib "Space Concordia") (part "Resistor"))
    )
    (comp (ref "R162")
      (value "100k")
      (footprint "R0603B")
      (description "Resistor")
      (fields (field (name "ALTIUM_VALUE") "100k"))
      (libsource (lib "Space Concordia") (part "Resistor"))
    )
    (comp (ref "R163")
      (value "0402 JUMPER")
      (footprint "RESC1005X40X25ML05T05")
      (description "READ THE NAME")
      (libsource (lib "Space Concordia") (part "CMP-009-00206-2"))
    )
    (comp (ref "R164")
      (value "0402 JUMPER")
      (footprint "RESC1005X40X25ML05T05")
      (description "READ THE NAME")
      (libsource (lib "Space Concordia") (part "CMP-009-00206-2"))
    )
    (comp (ref "R165")
      (value "27")
      (footprint "R0603B")
      (description "Resistor")
      (libsource (lib "Space Concordia") (part "Resistor"))
    )
    (comp (ref "R166")
      (value "27")
      (footprint "R0603B")
      (description "Resistor")
      (libsource (lib "Space Concordia") (part "Resistor"))
    )
    (comp (ref "R167")
      (value "0402 JUMPER")
      (footprint "RESC1005X40X25ML05T05")
      (description "READ THE NAME")
      (libsource (lib "Space Concordia") (part "CMP-009-00206-2"))
    )
    (comp (ref "R168")
      (value "0402 JUMPER")
      (footprint "RESC1005X40X25ML05T05")
      (description "READ THE NAME")
      (libsource (lib "Space Concordia") (part "CMP-009-00206-2"))
    )
    (comp (ref "R169")
      (value "DNP")
      (footprint "R0603B")
      (description "Resistor")
      (libsource (lib "Space Concordia") (part "Resistor"))
    )
    (comp (ref "R170")
      (value "DNP")
      (footprint "R0603B")
      (description "Resistor")
      (libsource (lib "Space Concordia") (part "Resistor"))
    )
    (comp (ref "R177")
      (value "1k")
      (footprint "R0603B")
      (description "Resistor")
      (fields (field (name "ALTIUM_VALUE") "1k"))
      (libsource (lib "Space Concordia") (part "Resistor"))
    )
    (comp (ref "R178")
      (value "1k")
      (footprint "R0603B")
      (description "Resistor")
      (fields (field (name "ALTIUM_VALUE") "1k"))
      (libsource (lib "Space Concordia") (part "Resistor"))
    )
    (comp (ref "R269")
      (value "33")
      (footprint "R0603B")
      (description "Resistor")
      (libsource (lib "Space Concordia") (part "Resistor"))
    )
    (comp (ref "R270")
      (value "33")
      (footprint "R0603B")
      (description "Resistor")
      (libsource (lib "Space Concordia") (part "Resistor"))
    )
    (comp (ref "R279")
      (value "33")
      (footprint "R0603B")
      (description "Resistor")
      (libsource (lib "Space Concordia") (part "Resistor"))
    )
    (comp (ref "R291")
      (value "33")
      (footprint "R0603B")
      (description "Resistor")
      (libsource (lib "Space Concordia") (part "Resistor"))
    )
    (comp (ref "R292")
      (value "33")
      (footprint "R0603B")
      (description "Resistor")
      (libsource (lib "Space Concordia") (part "Resistor"))
    )
    (comp (ref "R293")
      (value "33")
      (footprint "R0603B")
      (description "Resistor")
      (libsource (lib "Space Concordia") (part "Resistor"))
    )
    (comp (ref "R294")
      (value "33")
      (footprint "R0603B")
      (description "Resistor")
      (libsource (lib "Space Concordia") (part "Resistor"))
    )
    (comp (ref "R295")
      (value "33")
      (footprint "R0603B")
      (description "Resistor")
      (libsource (lib "Space Concordia") (part "Resistor"))
    )
    (comp (ref "U16")
      (value "AP22804AW5-7")
      (footprint "SOT95P285X140-5N")
      (description "SINGLE CHANNEL POWER DISTRIBUTION LOAD SWITCH, -40 to 85°C pF, RoHS")
      (libsource (lib "Space Concordia") (part "AP22804AW5-7"))
    )
    (comp (ref "U17")
      (value "MC74VHC1G135DFT2G-Q")
      (footprint "SOT65P210X110-5N")
      (description "Single 2-Input NAND Gate, Schmitt Trigger , Open Drain")
      (libsource (lib "Space Concordia") (part "MC74VHC1G135DFT2G-Q"))
    )
    (comp (ref "U18")
      (value "AP22804AW5-7")
      (footprint "SOT95P285X140-5N")
      (description "SINGLE CHANNEL POWER DISTRIBUTION LOAD SWITCH, -40 to 85°C pF, RoHS")
      (libsource (lib "Space Concordia") (part "AP22804AW5-7"))
    )
  )
  (nets
    (net (code "18") (name "/3V3_CAR_VCC_INH") (class "Default")
      (node (ref "U17") (pin "2") (pinfunction "A_2") (pintype "input"))
    )
    (net (code "21") (name "/3V3_CAR_VCC_nINH") (class "Default")
      (node (ref "R137") (pin "1") (pinfunction "1_1") (pintype "passive"))
      (node (ref "U17") (pin "4") (pinfunction "Y_4") (pintype "output"))
    )
    (net (code "22") (name "/3V3_CPU_FAN_TACHO") (class "Default")
      (node (ref "R156") (pin "2") (pinfunction "2_2") (pintype "passive"))
      (node (ref "R160") (pin "2") (pinfunction "2_2") (pintype "passive"))
    )
    (net (code "23") (name "/3V3_GPS_RXD") (class "Default")
      (node (ref "R164") (pin "2") (pinfunction "2_2") (pintype "passive"))
    )
    (net (code "24") (name "/3V3_GPS_TXD") (class "Default")
      (node (ref "R163") (pin "2") (pinfunction "2_2") (pintype "passive"))
    )
    (net (code "39") (name "/3V3_PWM0_CH0 (GPIO12)") (class "Default")
      (node (ref "R159") (pin "1") (pinfunction "1_1") (pintype "passive"))
    )
    (net (code "40") (name "/3V3_PWM0_CH1 (GPIO13)") (class "Default")
      (node (ref "R157") (pin "2") (pinfunction "2_2") (pintype "passive"))
      (node (ref "R158") (pin "2") (pinfunction "2_2") (pintype "passive"))
      (node (ref "R162") (pin "2") (pinfunction "2_2") (pintype "passive"))
    )
    (net (code "41") (name "/3V3_PWR_nFLT") (class "Default")
      (node (ref "R178") (pin "2") (pinfunction "2_2") (pintype "passive"))
    )
    (net (code "49") (name "/3V3_SPI1_MISO (GPIO19)") (class "Default")
      (node (ref "R141") (pin "2") (pinfunction "2_2") (pintype "passive"))
    )
    (net (code "50") (name "/3V3_SPI1_MOSI (GPIO20)") (class "Default")
      (node (ref "R140") (pin "2") (pinfunction "2_2") (pintype "passive"))
    )
    (net (code "51") (name "/3V3_SPI1_SCLK (GPIO21)") (class "Default")
      (node (ref "R142") (pin "2") (pinfunction "2_2") (pintype "passive"))
    )
    (net (code "53") (name "/3V3_SPI1_nCS1 (GPIO27)") (class "Default")
      (node (ref "R143") (pin "2") (pinfunction "2_2") (pintype "passive"))
    )
    (net (code "54") (name "/3V3_SPI1_nCS2 (GPIO16)") (class "Default")
      (node (ref "R146") (pin "2") (pinfunction "2_2") (pintype "passive"))
    )
    (net (code "55") (name "/3V3_SPI3_SCLK (GPIO7)") (class "Default")
      (node (ref "R148") (pin "2") (pinfunction "2_2") (pintype "passive"))
    )
    (net (code "56") (name "/3V3_TCAN1146_MISO") (class "Default")
      (node (ref "R141") (pin "1") (pinfunction "1_1") (pintype "passive"))
    )
    (net (code "57") (name "/3V3_TCAN1146_MOSI") (class "Default")
      (node (ref "R140") (pin "1") (pinfunction "1_1") (pintype "passive"))
    )
    (net (code "58") (name "/3V3_TCAN1146_SCLK") (class "Default")
      (node (ref "R142") (pin "1") (pinfunction "1_1") (pintype "passive"))
    )
    (net (code "59") (name "/3V3_TCAN1146_nCS") (class "Default")
      (node (ref "R143") (pin "1") (pinfunction "1_1") (pintype "passive"))
    )
    (net (code "60") (name "/3V3_UART0_RX (GPIO15)") (class "Default")
      (node (ref "R163") (pin "1") (pinfunction "1_1") (pintype "passive"))
    )
    (net (code "61") (name "/3V3_UART0_TX (GPIO14)") (class "Default")
      (node (ref "R164") (pin "1") (pinfunction "1_1") (pintype "passive"))
    )
    (net (code "62") (name "/3V3_VBUS_EN") (class "Default")
      (node (ref "R138") (pin "2") (pinfunction "2_2") (pintype "passive"))
      (node (ref "R150") (pin "2") (pinfunction "2_2") (pintype "passive"))
    )
    (net (code "65") (name "/3V3_nINH") (class "Default")
      (node (ref "R137") (pin "2") (pinfunction "2_2") (pintype "passive"))
    )
    (net (code "67") (name "/3V3_nINT") (class "Default")
      (node (ref "R146") (pin "1") (pinfunction "1_1") (pintype "passive"))
    )
    (net (code "68") (name "/3V3_nRST") (class "Default")
      (node (ref "R148") (pin "1") (pinfunction "1_1") (pintype "passive"))
    )
    (net (code "69") (name "/5V0_HDMI0_CEC") (class "Default")
      (node (ref "D28") (pin "1") (pinfunction "IO1_1") (pintype "bidirectional"))
      (node (ref "D28") (pin "10") (pinfunction "NC_10") (pintype "passive"))
      (node (ref "J4") (pin "13") (pinfunction "CEC_13") (pintype "output"))
    )
    (net (code "70") (name "/5V0_HDMI0_HOTP") (class "Default")
      (node (ref "D28") (pin "5") (pinfunction "IO4_5") (pintype "bidirectional"))
      (node (ref "D28") (pin "6") (pinfunction "NC_6") (pintype "passive"))
      (node (ref "J4") (pin "19") (pinfunction "HOTPLUG_19") (pintype "output"))
    )
    (net (code "71") (name "/5V0_HDMI0_SCL") (class "Default")
      (node (ref "D28") (pin "2") (pinfunction "IO2_2") (pintype "bidirectional"))
      (node (ref "D28") (pin "9") (pinfunction "NC_9") (pintype "passive"))
      (node (ref "J4") (pin "15") (pinfunction "SCL_15") (pintype "input"))
    )
    (net (code "72") (name "/5V0_HDMI0_SDA") (class "Default")
      (node (ref "D28") (pin "4") (pinfunction "IO3_4") (pintype "bidirectional"))
      (node (ref "D28") (pin "7") (pinfunction "NC_7") (pintype "passive"))
      (node (ref "J4") (pin "16") (pinfunction "SDA_16") (pintype "bidirectional"))
    )
    (net (code "73") (name "/5V0_HDMI1_CEC") (class "Default")
      (node (ref "D29") (pin "1") (pinfunction "IO1_1") (pintype "bidirectional"))
      (node (ref "D29") (pin "10") (pinfunction "NC_10") (pintype "passive"))
      (node (ref "J6") (pin "13") (pinfunction "CEC_13") (pintype "output"))
    )
    (net (code "74") (name "/5V0_HDMI1_HOTP") (class "Default")
      (node (ref "D29") (pin "5") (pinfunction "IO4_5") (pintype "bidirectional"))
      (node (ref "D29") (pin "6") (pinfunction "NC_6") (pintype "passive"))
      (node (ref "J6") (pin "19") (pinfunction "HOTPLUG_19") (pintype "output"))
    )
    (net (code "75") (name "/5V0_HDMI1_SCL") (class "Default")
      (node (ref "D29") (pin "2") (pinfunction "IO2_2") (pintype "bidirectional"))
      (node (ref "D29") (pin "9") (pinfunction "NC_9") (pintype "passive"))
      (node (ref "J6") (pin "15") (pinfunction "SCL_15") (pintype "input"))
    )
    (net (code "76") (name "/5V0_HDMI1_SDA") (class "Default")
      (node (ref "D29") (pin "4") (pinfunction "IO3_4") (pintype "bidirectional"))
      (node (ref "D29") (pin "7") (pinfunction "NC_7") (pintype "passive"))
      (node (ref "J6") (pin "16") (pinfunction "SDA_16") (pintype "bidirectional"))
    )
    (net (code "78") (name "/5V0_USB2_CC1") (class "Default")
      (node (ref "R167") (pin "1") (pinfunction "1_1") (pintype "passive"))
    )
    (net (code "79") (name "/5V0_USB2_CC2") (class "Default")
      (node (ref "R168") (pin "1") (pinfunction "1_1") (pintype "passive"))
    )
    (net (code "80") (name "/AMBIENT_TEMP") (class "Default")
      (node (ref "R144") (pin "2") (pinfunction "2_2") (pintype "passive"))
      (node (ref "R145") (pin "2") (pinfunction "2_2") (pintype "passive"))
    )
    (net (code "81") (name "/CAN_N") (class "Default")
      (node (ref "J3") (pin "24") (pinfunction "24_24") (pintype "passive"))
    )
    (net (code "82") (name "/CAN_P") (class "Default")
      (node (ref "J3") (pin "25") (pinfunction "25_25") (pintype "passive"))
    )
    (net (code "83") (name "/CHA_FAN_PWM") (class "Default")
      (node (ref "Q12") (pin "3") (pinfunction "D_3") (pintype "passive"))
      (node (ref "R153") (pin "2") (pinfunction "2_2") (pintype "passive"))
      (node (ref "R155") (pin "2") (pinfunction "2_2") (pintype "passive"))
    )
    (net (code "100") (name "/DBG_USB_N") (class "Default")
      (node (ref "C133") (pin "1") (pinfunction "1_1") (pintype "passive"))
      (node (ref "D20") (pin "4") (pinfunction "IO3_4") (pintype "bidirectional"))
      (node (ref "D20") (pin "7") (pinfunction "NC_7") (pintype "passive"))
      (node (ref "J17") (pin "A7") (pinfunction "D-_A_A7") (pintype "bidirectional"))
      (node (ref "R166") (pin "1") (pinfunction "1_1") (pintype "passive"))
    )
    (net (code "101") (name "/DBG_USB_P") (class "Default")
      (node (ref "C132") (pin "1") (pinfunction "1_1") (pintype "passive"))
      (node (ref "D20") (pin "2") (pinfunction "IO2_2") (pintype "bidirectional"))
      (node (ref "D20") (pin "9") (pinfunction "NC_9") (pintype "passive"))
      (node (ref "J17") (pin "A6") (pinfunction "D+_A_A6") (pintype "bidirectional"))
      (node (ref "R165") (pin "1") (pinfunction "1_1") (pintype "passive"))
    )
    (net (code "102") (name "/DISP0_5V") (class "Default")
      (node (ref "J4") (pin "18") (pinfunction "5V_18") (pintype "passive"))
      (node (ref "J5") (pin "1") (pinfunction "1_1") (pintype "passive"))
      (node (ref "U16") (pin "1") (pinfunction "VOUT_1") (pintype "power_in"))
    )
    (net (code "103") (name "/DISP1_5V") (class "Default")
      (node (ref "J6") (pin "18") (pinfunction "5V_18") (pintype "passive"))
      (node (ref "J7") (pin "1") (pinfunction "1_1") (pintype "passive"))
      (node (ref "U18") (pin "1") (pinfunction "VOUT_1") (pintype "power_in"))
    )
    (net (code "116") (name "/FL_N") (class "Default")
      (node (ref "J11") (pin "1") (pinfunction "1_1") (pintype "passive"))
      (node (ref "J3") (pin "2") (pinfunction "2_2") (pintype "passive"))
    )
    (net (code "117") (name "/FL_P") (class "Default")
      (node (ref "J11") (pin "2") (pinfunction "2_2") (pintype "passive"))
      (node (ref "J3") (pin "1") (pinfunction "1_1") (pintype "passive"))
    )
    (net (code "118") (name "/FR_N") (class "Default")
      (node (ref "J11") (pin "3") (pinfunction "3_3") (pintype "passive"))
      (node (ref "J3") (pin "13") (pinfunction "13_13") (pintype "passive"))
    )
    (net (code "119") (name "/FR_P") (class "Default")
      (node (ref "J11") (pin "4") (pinfunction "4_4") (pintype "passive"))
      (node (ref "J3") (pin "14") (pinfunction "14_14") (pintype "passive"))
    )
    (net (code "120") (name "/HDMI0_CK_N") (class "Default")
      (node (ref "D26") (pin "5") (pinfunction "IO4_5") (pintype "bidirectional"))
      (node (ref "D26") (pin "6") (pinfunction "NC_6") (pintype "passive"))
      (node (ref "J4") (pin "12") (pinfunction "CK_N_12") (pintype "bidirectional"))
    )
    (net (code "121") (name "/HDMI0_CK_P") (class "Default")
      (node (ref "D26") (pin "4") (pinfunction "IO3_4") (pintype "bidirectional"))
      (node (ref "D26") (pin "7") (pinfunction "NC_7") (pintype "passive"))
      (node (ref "J4") (pin "10") (pinfunction "CK_P_10") (pintype "bidirectional"))
    )
    (net (code "122") (name "/HDMI0_D0_N") (class "Default")
      (node (ref "D26") (pin "2") (pinfunction "IO2_2") (pintype "bidirectional"))
      (node (ref "D26") (pin "9") (pinfunction "NC_9") (pintype "passive"))
      (node (ref "J4") (pin "9") (pinfunction "D0_N_9") (pintype "bidirectional"))
    )
    (net (code "123") (name "/HDMI0_D0_P") (class "Default")
      (node (ref "D26") (pin "1") (pinfunction "IO1_1") (pintype "bidirectional"))
      (node (ref "D26") (pin "10") (pinfunction "NC_10") (pintype "passive"))
      (node (ref "J4") (pin "7") (pinfunction "D0_P_7") (pintype "bidirectional"))
    )
    (net (code "124") (name "/HDMI0_D1_N") (class "Default")
      (node (ref "D3") (pin "5") (pinfunction "IO4_5") (pintype "bidirectional"))
      (node (ref "D3") (pin "6") (pinfunction "NC_6") (pintype "passive"))
      (node (ref "J4") (pin "6") (pinfunction "D1_N_6") (pintype "bidirectional"))
    )
    (net (code "125") (name "/HDMI0_D1_P") (class "Default")
      (node (ref "D3") (pin "4") (pinfunction "IO3_4") (pintype "bidirectional"))
      (node (ref "D3") (pin "7") (pinfunction "NC_7") (pintype "passive"))
      (node (ref "J4") (pin "4") (pinfunction "D1_P_4") (pintype "bidirectional"))
    )
    (net (code "126") (name "/HDMI0_D2_N") (class "Default")
      (node (ref "D3") (pin "2") (pinfunction "IO2_2") (pintype "bidirectional"))
      (node (ref "D3") (pin "9") (pinfunction "NC_9") (pintype "passive"))
      (node (ref "J4") (pin "3") (pinfunction "D2_N_3") (pintype "bidirectional"))
    )
    (net (code "127") (name "/HDMI0_D2_P") (class "Default")
      (node (ref "D3") (pin "1") (pinfunction "IO1_1") (pintype "bidirectional"))
      (node (ref "D3") (pin "10") (pinfunction "NC_10") (pintype "passive"))
      (node (ref "J4") (pin "1") (pinfunction "D2_P_1") (pintype "bidirectional"))
    )
    (net (code "128") (name "/HDMI1_CK_N") (class "Default")
      (node (ref "D27") (pin "5") (pinfunction "IO4_5") (pintype "bidirectional"))
      (node (ref "D27") (pin "6") (pinfunction "NC_6") (pintype "passive"))
      (node (ref "J6") (pin "12") (pinfunction "CK_N_12") (pintype "bidirectional"))
    )
    (net (code "129") (name "/HDMI1_CK_P") (class "Default")
      (node (ref "D27") (pin "4") (pinfunction "IO3_4") (pintype "bidirectional"))
      (node (ref "D27") (pin "7") (pinfunction "NC_7") (pintype "passive"))
      (node (ref "J6") (pin "10") (pinfunction "CK_P_10") (pintype "bidirectional"))
    )
    (net (code "130") (name "/HDMI1_D0_N") (class "Default")
      (node (ref "D27") (pin "2") (pinfunction "IO2_2") (pintype "bidirectional"))
      (node (ref "D27") (pin "9") (pinfunction "NC_9") (pintype "passive"))
      (node (ref "J6") (pin "9") (pinfunction "D0_N_9") (pintype "bidirectional"))
    )
    (net (code "131") (name "/HDMI1_D0_P") (class "Default")
      (node (ref "D27") (pin "1") (pinfunction "IO1_1") (pintype "bidirectional"))
      (node (ref "D27") (pin "10") (pinfunction "NC_10") (pintype "passive"))
      (node (ref "J6") (pin "7") (pinfunction "D0_P_7") (pintype "bidirectional"))
    )
    (net (code "132") (name "/HDMI1_D1_N") (class "Default")
      (node (ref "D23") (pin "5") (pinfunction "IO4_5") (pintype "bidirectional"))
      (node (ref "D23") (pin "6") (pinfunction "NC_6") (pintype "passive"))
      (node (ref "J6") (pin "6") (pinfunction "D1_N_6") (pintype "bidirectional"))
    )
    (net (code "133") (name "/HDMI1_D1_P") (class "Default")
      (node (ref "D23") (pin "4") (pinfunction "IO3_4") (pintype "bidirectional"))
      (node (ref "D23") (pin "7") (pinfunction "NC_7") (pintype "passive"))
      (node (ref "J6") (pin "4") (pinfunction "D1_P_4") (pintype "bidirectional"))
    )
    (net (code "134") (name "/HDMI1_D2_N") (class "Default")
      (node (ref "D23") (pin "2") (pinfunction "IO2_2") (pintype "bidirectional"))
      (node (ref "D23") (pin "9") (pinfunction "NC_9") (pintype "passive"))
      (node (ref "J6") (pin "3") (pinfunction "D2_N_3") (pintype "bidirectional"))
    )
    (net (code "135") (name "/HDMI1_D2_P") (class "Default")
      (node (ref "D23") (pin "1") (pinfunction "IO1_1") (pintype "bidirectional"))
      (node (ref "D23") (pin "10") (pinfunction "NC_10") (pintype "passive"))
      (node (ref "J6") (pin "1") (pinfunction "D2_P_1") (pintype "bidirectional"))
    )
    (net (code "136") (name "/HV_CPU_FAN_PWM") (class "Default")
      (node (ref "R152") (pin "2") (pinfunction "2_2") (pintype "passive"))
      (node (ref "R154") (pin "2") (pinfunction "2_2") (pintype "passive"))
    )
    (net (code "138") (name "/LL_FR_L") (class "Default")
      (node (ref "J9") (pin "6") (pinfunction "6_6") (pintype "passive"))
    )
    (net (code "139") (name "/LL_FR_R") (class "Default")
      (node (ref "J9") (pin "8") (pinfunction "8_8") (pintype "passive"))
    )
    (net (code "140") (name "/LL_RR_L") (class "Default")
      (node (ref "J8") (pin "6") (pinfunction "6_6") (pintype "passive"))
    )
    (net (code "141") (name "/LL_RR_R") (class "Default")
      (node (ref "J8") (pin "8") (pinfunction "8_8") (pintype "passive"))
    )
    (net (code "142") (name "/MAX_M10M_RF_IN") (class "Default")
      (node (ref "D32") (pin "1") (pinfunction "IO1_1") (pintype "bidirectional"))
      (node (ref "D32") (pin "10") (pinfunction "NC_10") (pintype "passive"))
      (node (ref "J16") (pin "1") (pinfunction "RF_1") (pintype "passive"))
    )
    (net (code "144") (name "/MIC_P") (class "Default")
      (node (ref "J3") (pin "27") (pinfunction "27_27") (pintype "passive"))
    )
    (net (code "151") (name "/PRE_RC_DBG_USB_N") (class "Default")
      (node (ref "R166") (pin "2") (pinfunction "2_2") (pintype "passive"))
    )
    (net (code "152") (name "/PRE_RC_DBG_USB_P") (class "Default")
      (node (ref "R165") (pin "2") (pinfunction "2_2") (pintype "passive"))
    )
    (net (code "158") (name "/RF_A") (class "Default")
      (node (ref "J12") (pin "2") (pinfunction "2_2") (pintype "passive"))
    )
    (net (code "159") (name "/RF_B") (class "Default")
      (node (ref "J12") (pin "1") (pinfunction "1_1") (pintype "passive"))
    )
    (net (code "160") (name "/RF_C") (class "Default")
      (node (ref "J12") (pin "4") (pinfunction "4_4") (pintype "passive"))
    )
    (net (code "161") (name "/RF_D") (class "Default")
      (node (ref "J12") (pin "3") (pinfunction "3_3") (pintype "passive"))
    )
    (net (code "162") (name "/RL_N") (class "Default")
      (node (ref "J10") (pin "4") (pinfunction "4_4") (pintype "passive"))
      (node (ref "J3") (pin "3") (pinfunction "3_3") (pintype "passive"))
    )
    (net (code "163") (name "/RL_P") (class "Default")
      (node (ref "J10") (pin "3") (pinfunction "3_3") (pintype "passive"))
      (node (ref "J3") (pin "4") (pinfunction "4_4") (pintype "passive"))
    )
    (net (code "164") (name "/RR_N") (class "Default")
      (node (ref "J10") (pin "2") (pinfunction "2_2") (pintype "passive"))
      (node (ref "J3") (pin "5") (pinfunction "5_5") (pintype "passive"))
    )
    (net (code "165") (name "/RR_P") (class "Default")
      (node (ref "J10") (pin "1") (pinfunction "1_1") (pintype "passive"))
      (node (ref "J3") (pin "6") (pinfunction "6_6") (pintype "passive"))
    )
    (net (code "166") (name "/RXC") (class "Default")
      (node (ref "R269") (pin "1") (pinfunction "1_1") (pintype "passive"))
    )
    (net (code "167") (name "/RXC_1") (class "Default")
      (node (ref "R294") (pin "2") (pinfunction "2_2") (pintype "passive"))
    )
    (net (code "168") (name "/RXD0") (class "Default")
      (node (ref "R52") (pin "1") (pinfunction "1_1") (pintype "passive"))
    )
    (net (code "169") (name "/RXD0_1") (class "Default")
      (node (ref "R279") (pin "2") (pinfunction "2_2") (pintype "passive"))
    )
    (net (code "170") (name "/RXD1") (class "Default")
      (node (ref "R53") (pin "1") (pinfunction "1_1") (pintype "passive"))
    )
    (net (code "171") (name "/RXD1_1") (class "Default")
      (node (ref "R291") (pin "2") (pinfunction "2_2") (pintype "passive"))
    )
    (net (code "172") (name "/RXD2") (class "Default")
      (node (ref "R54") (pin "1") (pinfunction "1_1") (pintype "passive"))
    )
    (net (code "173") (name "/RXD2_1") (class "Default")
      (node (ref "R292") (pin "2") (pinfunction "2_2") (pintype "passive"))
    )
    (net (code "174") (name "/RXD3") (class "Default")
      (node (ref "R55") (pin "1") (pinfunction "1_1") (pintype "passive"))
    )
    (net (code "175") (name "/RXD3_1") (class "Default")
      (node (ref "R293") (pin "2") (pinfunction "2_2") (pintype "passive"))
    )
    (net (code "176") (name "/RX_CTL") (class "Default")
      (node (ref "R270") (pin "1") (pinfunction "1_1") (pintype "passive"))
    )
    (net (code "177") (name "/RX_CTL_1") (class "Default")
      (node (ref "R295") (pin "2") (pinfunction "2_2") (pintype "passive"))
    )
    (net (code "186") (name "/SUB_P") (class "Default")
      (node (ref "J3") (pin "28") (pinfunction "28_28") (pintype "passive"))
    )
    (net (code "187") (name "/TRX_CON_N") (class "Default")
      (node (ref "D24") (pin "2") (pinfunction "IO2_2") (pintype "bidirectional"))
      (node (ref "D24") (pin "9") (pinfunction "NC_9") (pintype "passive"))
      (node (ref "J15") (pin "1") (pinfunction "TX_P_1") (pintype "passive"))
    )
    (net (code "188") (name "/TRX_CON_P") (class "Default")
      (node (ref "D24") (pin "4") (pinfunction "IO3_4") (pintype "bidirectional"))
      (node (ref "D24") (pin "7") (pinfunction "NC_7") (pintype "passive"))
      (node (ref "J15") (pin "2") (pinfunction "TX_N_2") (pintype "passive"))
    )
    (net (code "189") (name "/TXC") (class "Default")
      (node (ref "R294") (pin "1") (pinfunction "1_1") (pintype "passive"))
    )
    (net (code "190") (name "/TXC_1") (class "Default")
      (node (ref "R269") (pin "2") (pinfunction "2_2") (pintype "passive"))
    )
    (net (code "191") (name "/TXD0") (class "Default")
      (node (ref "R279") (pin "1") (pinfunction "1_1") (pintype "passive"))
    )
    (net (code "192") (name "/TXD0_1") (class "Default")
      (node (ref "R52") (pin "2") (pinfunction "2_2") (pintype "passive"))
    )
    (net (code "193") (name "/TXD1") (class "Default")
      (node (ref "R291") (pin "1") (pinfunction "1_1") (pintype "passive"))
    )
    (net (code "194") (name "/TXD1_1") (class "Default")
      (node (ref "R53") (pin "2") (pinfunction "2_2") (pintype "passive"))
    )
    (net (code "195") (name "/TXD2") (class "Default")
      (node (ref "R292") (pin "1") (pinfunction "1_1") (pintype "passive"))
    )
    (net (code "196") (name "/TXD2_1") (class "Default")
      (node (ref "R54") (pin "2") (pinfunction "2_2") (pintype "passive"))
    )
    (net (code "197") (name "/TXD3") (class "Default")
      (node (ref "R293") (pin "1") (pinfunction "1_1") (pintype "passive"))
    )
    (net (code "198") (name "/TXD3_1") (class "Default")
      (node (ref "R55") (pin "2") (pinfunction "2_2") (pintype "passive"))
    )
    (net (code "199") (name "/TX_CTL") (class "Default")
      (node (ref "R295") (pin "1") (pinfunction "1_1") (pintype "passive"))
    )
    (net (code "200") (name "/TX_CTL_1") (class "Default")
      (node (ref "R270") (pin "2") (pinfunction "2_2") (pintype "passive"))
    )
    (net (code "201") (name "/USB2_CC1") (class "Default")
      (node (ref "D20") (pin "1") (pinfunction "IO1_1") (pintype "bidirectional"))
      (node (ref "D20") (pin "10") (pinfunction "NC_10") (pintype "passive"))
      (node (ref "J17") (pin "A5") (pinfunction "CC1_A_A5") (pintype "bidirectional"))
      (node (ref "R167") (pin "2") (pinfunction "2_2") (pintype "passive"))
      (node (ref "R169") (pin "1") (pinfunction "1_1") (pintype "passive"))
    )
    (net (code "202") (name "/USB2_CC2") (class "Default")
      (node (ref "D20") (pin "5") (pinfunction "IO4_5") (pintype "bidirectional"))
      (node (ref "D20") (pin "6") (pinfunction "NC_6") (pintype "passive"))
      (node (ref "J17") (pin "B5") (pinfunction "CC1_B_B5") (pintype "bidirectional"))
      (node (ref "R168") (pin "2") (pinfunction "2_2") (pintype "passive"))
      (node (ref "R170") (pin "1") (pinfunction "1_1") (pintype "passive"))
    )
    (net (code "207") (name "/USB2_TYPEA_DISP0_D_N") (class "Default")
      (node (ref "D30") (pin "2") (pinfunction "IO2_2") (pintype "bidirectional"))
      (node (ref "D30") (pin "9") (pinfunction "NC_9") (pintype "passive"))
      (node (ref "J5") (pin "2") (pinfunction "2_2") (pintype "passive"))
    )
    (net (code "208") (name "/USB2_TYPEA_DISP0_D_P") (class "Default")
      (node (ref "D30") (pin "4") (pinfunction "IO3_4") (pintype "bidirectional"))
      (node (ref "D30") (pin "7") (pinfunction "NC_7") (pintype "passive"))
      (node (ref "J5") (pin "3") (pinfunction "3_3") (pintype "passive"))
    )
    (net (code "209") (name "/USB2_TYPEA_DISP1_D_N") (class "Default")
      (node (ref "D31") (pin "2") (pinfunction "IO2_2") (pintype "bidirectional"))
      (node (ref "D31") (pin "9") (pinfunction "NC_9") (pintype "passive"))
      (node (ref "J7") (pin "2") (pinfunction "2_2") (pintype "passive"))
    )
    (net (code "210") (name "/USB2_TYPEA_DISP1_D_P") (class "Default")
      (node (ref "D31") (pin "4") (pinfunction "IO3_4") (pintype "bidirectional"))
      (node (ref "D31") (pin "7") (pinfunction "NC_7") (pintype "passive"))
      (node (ref "J7") (pin "3") (pinfunction "3_3") (pintype "passive"))
    )
    (net (code "229") (name "3V3_AUX") (class "Default")
      (node (ref "F1") (pin "2") (pinfunction "2_2") (pintype "passive"))
      (node (ref "F11") (pin "2") (pinfunction "2_2") (pintype "passive"))
      (node (ref "F12") (pin "2") (pinfunction "2_2") (pintype "passive"))
      (node (ref "F14") (pin "2") (pinfunction "2_2") (pintype "passive"))
      (node (ref "F19") (pin "2") (pinfunction "2_2") (pintype "passive"))
      (node (ref "J18") (pin "1") (pinfunction "1_1") (pintype "passive"))
    )
    (net (code "230") (name "3V3_CAN") (class "Default")
      (node (ref "F25") (pin "2") (pinfunction "2_2") (pintype "passive"))
    )
    (net (code "231") (name "3V3_DES_0") (class "Default")
      (node (ref "F12") (pin "1") (pinfunction "1_1") (pintype "passive"))
    )
    (net (code "232") (name "3V3_GPS") (class "Default")
      (node (ref "F21") (pin "2") (pinfunction "2_2") (pintype "passive"))
    )
    (net (code "233") (name "3V3_LAN") (class "Default")
      (node (ref "F19") (pin "1") (pinfunction "1_1") (pintype "passive"))
    )
    (net (code "234") (name "3V3_LED") (class "Default")
      (node (ref "D9") (pin "2") (pinfunction "A_2") (pintype "passive"))
      (node (ref "D9") (pin "3") (pinfunction "A_3") (pintype "passive"))
      (node (ref "J18") (pin "2") (pinfunction "2_2") (pintype "passive"))
    )
    (net (code "235") (name "3V3_M2") (class "Default")
      (node (ref "F1") (pin "1") (pinfunction "1_1") (pintype "passive"))
    )
    (net (code "236") (name "3V3_MAIN") (class "Default")
      (node (ref "F21") (pin "1") (pinfunction "1_1") (pintype "passive"))
      (node (ref "F23") (pin "1") (pinfunction "1_1") (pintype "passive"))
      (node (ref "F25") (pin "1") (pinfunction "1_1") (pintype "passive"))
      (node (ref "R160") (pin "1") (pinfunction "1_1") (pintype "passive"))
      (node (ref "R162") (pin "1") (pinfunction "1_1") (pintype "passive"))
    )
    (net (code "237") (name "3V3_PWR") (class "Default")
      (node (ref "C119") (pin "1") (pinfunction "1_1") (pintype "passive"))
      (node (ref "F14") (pin "1") (pinfunction "1_1") (pintype "passive"))
      (node (ref "R144") (pin "1") (pinfunction "1_1") (pintype "passive"))
      (node (ref "U17") (pin "5") (pinfunction "VCC_5") (pintype "power_in"))
    )
    (net (code "238") (name "3V3_SD") (class "Default")
      (node (ref "F23") (pin "2") (pinfunction "2_2") (pintype "passive"))
    )
    (net (code "239") (name "3V3_USB") (class "Default")
      (node (ref "F11") (pin "1") (pinfunction "1_1") (pintype "passive"))
    )
    (net (code "240") (name "5V0_CAN") (class "Default")
      (node (ref "F24") (pin "2") (pinfunction "2_2") (pintype "passive"))
    )
    (net (code "241") (name "5V0_DAC") (class "Default")
      (node (ref "F8") (pin "1") (pinfunction "1_1") (pintype "passive"))
    )
    (net (code "242") (name "5V0_DISP_0") (class "Default")
      (node (ref "F10") (pin "1") (pinfunction "1_1") (pintype "passive"))
      (node (ref "U16") (pin "5") (pinfunction "VIN_5") (pintype "power_in"))
    )
    (net (code "243") (name "5V0_DISP_1") (class "Default")
      (node (ref "F13") (pin "1") (pinfunction "1_1") (pintype "passive"))
      (node (ref "U18") (pin "5") (pinfunction "VIN_5") (pintype "power_in"))
    )
    (net (code "244") (name "5V0_MAIN") (class "Default")
      (node (ref "F10") (pin "2") (pinfunction "2_2") (pintype "passive"))
      (node (ref "F13") (pin "2") (pinfunction "2_2") (pintype "passive"))
      (node (ref "F16") (pin "2") (pinfunction "2_2") (pintype "passive"))
      (node (ref "F17") (pin "2") (pinfunction "2_2") (pintype "passive"))
      (node (ref "F24") (pin "1") (pinfunction "1_1") (pintype "passive"))
      (node (ref "F8") (pin "2") (pinfunction "2_2") (pintype "passive"))
      (node (ref "F9") (pin "2") (pinfunction "2_2") (pintype "passive"))
      (node (ref "R154") (pin "1") (pinfunction "1_1") (pintype "passive"))
      (node (ref "R155") (pin "1") (pinfunction "1_1") (pintype "passive"))
    )
    (net (code "245") (name "5V0_RPI") (class "Default")
      (node (ref "F9") (pin "1") (pinfunction "1_1") (pintype "passive"))
    )
    (net (code "246") (name "12V0_PoC") (class "Default")
      (node (ref "C260") (pin "1") (pinfunction "1_1") (pintype "passive"))
      (node (ref "C261") (pin "1") (pinfunction "1_1") (pintype "passive"))
      (node (ref "C262") (pin "1") (pinfunction "1_1") (pintype "passive"))
      (node (ref "C263") (pin "1") (pinfunction "1_1") (pintype "passive"))
    )
    (net (code "247") (name "AMP_VCC") (class "Default")
      (node (ref "J8") (pin "1") (pinfunction "1_1") (pintype "passive"))
      (node (ref "J8") (pin "2") (pinfunction "2_2") (pintype "passive"))
      (node (ref "J8") (pin "3") (pinfunction "3_3") (pintype "passive"))
      (node (ref "J9") (pin "1") (pinfunction "1_1") (pintype "passive"))
      (node (ref "J9") (pin "2") (pinfunction "2_2") (pintype "passive"))
      (node (ref "J9") (pin "3") (pinfunction "3_3") (pintype "passive"))
    )
    (net (code "248") (name "APM_VCC") (class "Default")
      (node (ref "J3") (pin "10") (pinfunction "10_10") (pintype "passive"))
      (node (ref "J3") (pin "21") (pinfunction "21_21") (pintype "passive"))
      (node (ref "J3") (pin "33") (pinfunction "33_33") (pintype "passive"))
      (node (ref "R147") (pin "2") (pinfunction "2_2") (pintype "passive"))
    )
    (net (code "249") (name "CAR_VCC") (class "Default")
      (node (ref "J3") (pin "12") (pinfunction "12_12") (pintype "passive"))
      (node (ref "J3") (pin "23") (pinfunction "23_23") (pintype "passive"))
      (node (ref "J3") (pin "35") (pinfunction "35_35") (pintype "passive"))
    )
    (net (code "250") (name "CHASSIS") (class "Default")
      (node (ref "C120") (pin "2") (pinfunction "2_2") (pintype "passive"))
      (node (ref "C121") (pin "2") (pinfunction "2_2") (pintype "passive"))
      (node (ref "C122") (pin "2") (pinfunction "2_2") (pintype "passive"))
      (node (ref "C123") (pin "2") (pinfunction "2_2") (pintype "passive"))
      (node (ref "C124") (pin "2") (pinfunction "2_2") (pintype "passive"))
      (node (ref "C125") (pin "2") (pinfunction "2_2") (pintype "passive"))
      (node (ref "C126") (pin "2") (pinfunction "2_2") (pintype "passive"))
      (node (ref "C127") (pin "2") (pinfunction "2_2") (pintype "passive"))
      (node (ref "C128") (pin "2") (pinfunction "2_2") (pintype "passive"))
      (node (ref "C129") (pin "2") (pinfunction "2_2") (pintype "passive"))
      (node (ref "C130") (pin "2") (pinfunction "2_2") (pintype "passive"))
      (node (ref "C131") (pin "2") (pinfunction "2_2") (pintype "passive"))
      (node (ref "MH1") (pin "1") (pinfunction "MH_1") (pintype "passive"))
      (node (ref "MH1") (pin "2") (pinfunction "V1_2") (pintype "passive"))
      (node (ref "MH1") (pin "3") (pinfunction "V2_3") (pintype "passive"))
      (node (ref "MH1") (pin "4") (pinfunction "V3_4") (pintype "passive"))
      (node (ref "MH1") (pin "5") (pinfunction "V4_5") (pintype "passive"))
      (node (ref "MH1") (pin "6") (pinfunction "V5_6") (pintype "passive"))
      (node (ref "MH1") (pin "7") (pinfunction "V6_7") (pintype "passive"))
      (node (ref "MH10") (pin "1") (pinfunction "MH_1") (pintype "passive"))
      (node (ref "MH10") (pin "2") (pinfunction "V1_2") (pintype "passive"))
      (node (ref "MH10") (pin "3") (pinfunction "V2_3") (pintype "passive"))
      (node (ref "MH10") (pin "4") (pinfunction "V3_4") (pintype "passive"))
      (node (ref "MH10") (pin "5") (pinfunction "V4_5") (pintype "passive"))
      (node (ref "MH10") (pin "6") (pinfunction "V5_6") (pintype "passive"))
      (node (ref "MH10") (pin "7") (pinfunction "V6_7") (pintype "passive"))
      (node (ref "MH11") (pin "1") (pinfunction "MH_1") (pintype "passive"))
      (node (ref "MH11") (pin "2") (pinfunction "V1_2") (pintype "passive"))
      (node (ref "MH11") (pin "3") (pinfunction "V2_3") (pintype "passive"))
      (node (ref "MH11") (pin "4") (pinfunction "V3_4") (pintype "passive"))
      (node (ref "MH11") (pin "5") (pinfunction "V4_5") (pintype "passive"))
      (node (ref "MH11") (pin "6") (pinfunction "V5_6") (pintype "passive"))
      (node (ref "MH11") (pin "7") (pinfunction "V6_7") (pintype "passive"))
      (node (ref "MH12") (pin "1") (pinfunction "MH_1") (pintype "passive"))
      (node (ref "MH12") (pin "2") (pinfunction "V1_2") (pintype "passive"))
      (node (ref "MH12") (pin "3") (pinfunction "V2_3") (pintype "passive"))
      (node (ref "MH12") (pin "4") (pinfunction "V3_4") (pintype "passive"))
      (node (ref "MH12") (pin "5") (pinfunction "V4_5") (pintype "passive"))
      (node (ref "MH12") (pin "6") (pinfunction "V5_6") (pintype "passive"))
      (node (ref "MH12") (pin "7") (pinfunction "V6_7") (pintype "passive"))
      (node (ref "MH13") (pin "1") (pinfunction "MH_1") (pintype "passive"))
      (node (ref "MH13") (pin "2") (pinfunction "V1_2") (pintype "passive"))
      (node (ref "MH13") (pin "3") (pinfunction "V2_3") (pintype "passive"))
      (node (ref "MH13") (pin "4") (pinfunction "V3_4") (pintype "passive"))
      (node (ref "MH13") (pin "5") (pinfunction "V4_5") (pintype "passive"))
      (node (ref "MH13") (pin "6") (pinfunction "V5_6") (pintype "passive"))
      (node (ref "MH13") (pin "7") (pinfunction "V6_7") (pintype "passive"))
      (node (ref "MH14") (pin "1") (pinfunction "MH_1") (pintype "passive"))
      (node (ref "MH14") (pin "2") (pinfunction "V1_2") (pintype "passive"))
      (node (ref "MH14") (pin "3") (pinfunction "V2_3") (pintype "passive"))
      (node (ref "MH14") (pin "4") (pinfunction "V3_4") (pintype "passive"))
      (node (ref "MH14") (pin "5") (pinfunction "V4_5") (pintype "passive"))
      (node (ref "MH14") (pin "6") (pinfunction "V5_6") (pintype "passive"))
      (node (ref "MH14") (pin "7") (pinfunction "V6_7") (pintype "passive"))
      (node (ref "MH2") (pin "1") (pinfunction "MH_1") (pintype "passive"))
      (node (ref "MH2") (pin "2") (pinfunction "V1_2") (pintype "passive"))
      (node (ref "MH2") (pin "3") (pinfunction "V2_3") (pintype "passive"))
      (node (ref "MH2") (pin "4") (pinfunction "V3_4") (pintype "passive"))
      (node (ref "MH2") (pin "5") (pinfunction "V4_5") (pintype "passive"))
      (node (ref "MH2") (pin "6") (pinfunction "V5_6") (pintype "passive"))
      (node (ref "MH2") (pin "7") (pinfunction "V6_7") (pintype "passive"))
      (node (ref "MH3") (pin "1") (pinfunction "MH_1") (pintype "passive"))
      (node (ref "MH3") (pin "2") (pinfunction "V1_2") (pintype "passive"))
      (node (ref "MH3") (pin "3") (pinfunction "V2_3") (pintype "passive"))
      (node (ref "MH3") (pin "4") (pinfunction "V3_4") (pintype "passive"))
      (node (ref "MH3") (pin "5") (pinfunction "V4_5") (pintype "passive"))
      (node (ref "MH3") (pin "6") (pinfunction "V5_6") (pintype "passive"))
      (node (ref "MH3") (pin "7") (pinfunction "V6_7") (pintype "passive"))
      (node (ref "MH4") (pin "1") (pinfunction "MH_1") (pintype "passive"))
      (node (ref "MH4") (pin "2") (pinfunction "V1_2") (pintype "passive"))
      (node (ref "MH4") (pin "3") (pinfunction "V2_3") (pintype "passive"))
      (node (ref "MH4") (pin "4") (pinfunction "V3_4") (pintype "passive"))
      (node (ref "MH4") (pin "5") (pinfunction "V4_5") (pintype "passive"))
      (node (ref "MH4") (pin "6") (pinfunction "V5_6") (pintype "passive"))
      (node (ref "MH4") (pin "7") (pinfunction "V6_7") (pintype "passive"))
      (node (ref "MH5") (pin "1") (pinfunction "MH_1") (pintype "passive"))
      (node (ref "MH5") (pin "2") (pinfunction "V1_2") (pintype "passive"))
      (node (ref "MH5") (pin "3") (pinfunction "V2_3") (pintype "passive"))
      (node (ref "MH5") (pin "4") (pinfunction "V3_4") (pintype "passive"))
      (node (ref "MH5") (pin "5") (pinfunction "V4_5") (pintype "passive"))
      (node (ref "MH5") (pin "6") (pinfunction "V5_6") (pintype "passive"))
      (node (ref "MH5") (pin "7") (pinfunction "V6_7") (pintype "passive"))
      (node (ref "MH6") (pin "1") (pinfunction "MH_1") (pintype "passive"))
      (node (ref "MH6") (pin "2") (pinfunction "V1_2") (pintype "passive"))
      (node (ref "MH6") (pin "3") (pinfunction "V2_3") (pintype "passive"))
      (node (ref "MH6") (pin "4") (pinfunction "V3_4") (pintype "passive"))
      (node (ref "MH6") (pin "5") (pinfunction "V4_5") (pintype "passive"))
      (node (ref "MH6") (pin "6") (pinfunction "V5_6") (pintype "passive"))
      (node (ref "MH6") (pin "7") (pinfunction "V6_7") (pintype "passive"))
      (node (ref "MH7") (pin "1") (pinfunction "MH_1") (pintype "passive"))
      (node (ref "MH7") (pin "2") (pinfunction "V1_2") (pintype "passive"))
      (node (ref "MH7") (pin "3") (pinfunction "V2_3") (pintype "passive"))
      (node (ref "MH7") (pin "4") (pinfunction "V3_4") (pintype "passive"))
      (node (ref "MH7") (pin "5") (pinfunction "V4_5") (pintype "passive"))
      (node (ref "MH7") (pin "6") (pinfunction "V5_6") (pintype "passive"))
      (node (ref "MH7") (pin "7") (pinfunction "V6_7") (pintype "passive"))
      (node (ref "MH8") (pin "1") (pinfunction "MH_1") (pintype "passive"))
      (node (ref "MH8") (pin "2") (pinfunction "V1_2") (pintype "passive"))
      (node (ref "MH8") (pin "3") (pinfunction "V2_3") (pintype "passive"))
      (node (ref "MH8") (pin "4") (pinfunction "V3_4") (pintype "passive"))
      (node (ref "MH8") (pin "5") (pinfunction "V4_5") (pintype "passive"))
      (node (ref "MH8") (pin "6") (pinfunction "V5_6") (pintype "passive"))
      (node (ref "MH8") (pin "7") (pinfunction "V6_7") (pintype "passive"))
      (node (ref "MH9") (pin "1") (pinfunction "MH_1") (pintype "passive"))
      (node (ref "MH9") (pin "2") (pinfunction "V1_2") (pintype "passive"))
      (node (ref "MH9") (pin "3") (pinfunction "V2_3") (pintype "passive"))
      (node (ref "MH9") (pin "4") (pinfunction "V3_4") (pintype "passive"))
      (node (ref "MH9") (pin "5") (pinfunction "V4_5") (pintype "passive"))
      (node (ref "MH9") (pin "6") (pinfunction "V5_6") (pintype "passive"))
      (node (ref "MH9") (pin "7") (pinfunction "V6_7") (pintype "passive"))
    )
    (net (code "251") (name "FAKRA_GND") (class "Default")
      (node (ref "C128") (pin "1") (pinfunction "1_1") (pintype "passive"))
      (node (ref "C129") (pin "1") (pinfunction "1_1") (pintype "passive"))
      (node (ref "C130") (pin "1") (pinfunction "1_1") (pintype "passive"))
      (node (ref "C131") (pin "1") (pinfunction "1_1") (pintype "passive"))
      (node (ref "J16") (pin "2") (pinfunction "SHIELD_2") (pintype "passive"))
    )
    (net (code "252") (name "GND") (class "Default")
      (node (ref "C119") (pin "2") (pinfunction "2_2") (pintype "passive"))
      (node (ref "C132") (pin "2") (pinfunction "2_2") (pintype "passive"))
      (node (ref "C133") (pin "2") (pinfunction "2_2") (pintype "passive"))
      (node (ref "C260") (pin "2") (pinfunction "2_2") (pintype "passive"))
      (node (ref "C261") (pin "2") (pinfunction "2_2") (pintype "passive"))
      (node (ref "C262") (pin "2") (pinfunction "2_2") (pintype "passive"))
      (node (ref "C263") (pin "2") (pinfunction "2_2") (pintype "passive"))
      (node (ref "D20") (pin "3") (pinfunction "GND_3") (pintype "power_in"))
      (node (ref "D20") (pin "8") (pinfunction "GND_8") (pintype "power_in"))
      (node (ref "D23") (pin "3") (pinfunction "GND_3") (pintype "power_in"))
      (node (ref "D23") (pin "8") (pinfunction "GND_8") (pintype "power_in"))
      (node (ref "D24") (pin "3") (pinfunction "GND_3") (pintype "power_in"))
      (node (ref "D24") (pin "8") (pinfunction "GND_8") (pintype "power_in"))
      (node (ref "D26") (pin "3") (pinfunction "GND_3") (pintype "power_in"))
      (node (ref "D26") (pin "8") (pinfunction "GND_8") (pintype "power_in"))
      (node (ref "D27") (pin "3") (pinfunction "GND_3") (pintype "power_in"))
      (node (ref "D27") (pin "8") (pinfunction "GND_8") (pintype "power_in"))
      (node (ref "D28") (pin "3") (pinfunction "GND_3") (pintype "power_in"))
      (node (ref "D28") (pin "8") (pinfunction "GND_8") (pintype "power_in"))
      (node (ref "D29") (pin "3") (pinfunction "GND_3") (pintype "power_in"))
      (node (ref "D29") (pin "8") (pinfunction "GND_8") (pintype "power_in"))
      (node (ref "D3") (pin "3") (pinfunction "GND_3") (pintype "power_in"))
      (node (ref "D3") (pin "8") (pinfunction "GND_8") (pintype "power_in"))
      (node (ref "D30") (pin "3") (pinfunction "GND_3") (pintype "power_in"))
      (node (ref "D30") (pin "8") (pinfunction "GND_8") (pintype "power_in"))
      (node (ref "D31") (pin "3") (pinfunction "GND_3") (pintype "power_in"))
      (node (ref "D31") (pin "8") (pinfunction "GND_8") (pintype "power_in"))
      (node (ref "D32") (pin "3") (pinfunction "GND_3") (pintype "power_in"))
      (node (ref "D32") (pin "8") (pinfunction "GND_8") (pintype "power_in"))
      (node (ref "J13") (pin "3") (pinfunction "3_3") (pintype "passive"))
      (node (ref "J13") (pin "5") (pinfunction "MNT_1_5") (pintype "passive"))
      (node (ref "J13") (pin "6") (pinfunction "MNT_2_6") (pintype "passive"))
      (node (ref "J14") (pin "3") (pinfunction "3_3") (pintype "passive"))
      (node (ref "J14") (pin "5") (pinfunction "MNT_1_5") (pintype "passive"))
      (node (ref "J14") (pin "6") (pinfunction "MNT_2_6") (pintype "passive"))
      (node (ref "J17") (pin "A1_B12") (pinfunction "GND_A1_B12") (pintype "power_in"))
      (node (ref "J17") (pin "B1_A12") (pinfunction "GND_B1_A12") (pintype "power_in"))
      (node (ref "J17") (pin "SH1") (pinfunction "SHIELD_SH1") (pintype "passive"))
      (node (ref "J17") (pin "SH2") (pinfunction "SHIELD_SH2") (pintype "passive"))
      (node (ref "J17") (pin "SH3") (pinfunction "SHIELD_SH3") (pintype "passive"))
      (node (ref "J17") (pin "SH4") (pinfunction "SHIELD_SH4") (pintype "passive"))
      (node (ref "J3") (pin "11") (pinfunction "11_11") (pintype "passive"))
      (node (ref "J3") (pin "20") (pinfunction "20_20") (pintype "passive"))
      (node (ref "J3") (pin "22") (pinfunction "22_22") (pintype "passive"))
      (node (ref "J3") (pin "32") (pinfunction "32_32") (pintype "passive"))
      (node (ref "J3") (pin "34") (pinfunction "34_34") (pintype "passive"))
      (node (ref "J3") (pin "9") (pinfunction "9_9") (pintype "passive"))
      (node (ref "J4") (pin "11") (pinfunction "GND_11") (pintype "passive"))
      (node (ref "J4") (pin "17") (pinfunction "GND_17") (pintype "passive"))
      (node (ref "J4") (pin "2") (pinfunction "GND_2") (pintype "passive"))
      (node (ref "J4") (pin "5") (pinfunction "GND_5") (pintype "passive"))
      (node (ref "J4") (pin "8") (pinfunction "GND_8") (pintype "passive"))
      (node (ref "J4") (pin "SH1") (pinfunction "SHIELD1_SH1") (pintype "passive"))
      (node (ref "J4") (pin "SH2") (pinfunction "SHIELD2_SH2") (pintype "passive"))
      (node (ref "J4") (pin "SH3") (pinfunction "SHIELD3_SH3") (pintype "passive"))
      (node (ref "J4") (pin "SH4") (pinfunction "SHIELD4_SH4") (pintype "passive"))
      (node (ref "J5") (pin "4") (pinfunction "4_4") (pintype "passive"))
      (node (ref "J5") (pin "5") (pinfunction "MNT_1_5") (pintype "passive"))
      (node (ref "J5") (pin "6") (pinfunction "MNT_2_6") (pintype "passive"))
      (node (ref "J6") (pin "11") (pinfunction "GND_11") (pintype "passive"))
      (node (ref "J6") (pin "17") (pinfunction "GND_17") (pintype "passive"))
      (node (ref "J6") (pin "2") (pinfunction "GND_2") (pintype "passive"))
      (node (ref "J6") (pin "5") (pinfunction "GND_5") (pintype "passive"))
      (node (ref "J6") (pin "8") (pinfunction "GND_8") (pintype "passive"))
      (node (ref "J6") (pin "SH1") (pinfunction "SHIELD1_SH1") (pintype "passive"))
      (node (ref "J6") (pin "SH2") (pinfunction "SHIELD2_SH2") (pintype "passive"))
      (node (ref "J6") (pin "SH3") (pinfunction "SHIELD3_SH3") (pintype "passive"))
      (node (ref "J6") (pin "SH4") (pinfunction "SHIELD4_SH4") (pintype "passive"))
      (node (ref "J7") (pin "4") (pinfunction "4_4") (pintype "passive"))
      (node (ref "J7") (pin "5") (pinfunction "MNT_1_5") (pintype "passive"))
      (node (ref "J7") (pin "6") (pinfunction "MNT_2_6") (pintype "passive"))
      (node (ref "J8") (pin "4") (pinfunction "4_4") (pintype "passive"))
      (node (ref "J8") (pin "5") (pinfunction "5_5") (pintype "passive"))
      (node (ref "J8") (pin "7") (pinfunction "7_7") (pintype "passive"))
      (node (ref "J9") (pin "4") (pinfunction "4_4") (pintype "passive"))
      (node (ref "J9") (pin "5") (pinfunction "5_5") (pintype "passive"))
      (node (ref "J9") (pin "7") (pinfunction "7_7") (pintype "passive"))
      (node (ref "Q12") (pin "2") (pinfunction "S_2") (pintype "passive"))
      (node (ref "R139") (pin "1") (pinfunction "1_1") (pintype "passive"))
      (node (ref "R145") (pin "1") (pinfunction "1_1") (pintype "passive"))
      (node (ref "R149") (pin "1") (pinfunction "1_1") (pintype "passive"))
      (node (ref "R151") (pin "1") (pinfunction "1_1") (pintype "passive"))
      (node (ref "R158") (pin "1") (pinfunction "1_1") (pintype "passive"))
      (node (ref "R161") (pin "2") (pinfunction "2_2") (pintype "passive"))
      (node (ref "R169") (pin "2") (pinfunction "2_2") (pintype "passive"))
      (node (ref "R170") (pin "2") (pinfunction "2_2") (pintype "passive"))
      (node (ref "R177") (pin "2") (pinfunction "2_2") (pintype "passive"))
      (node (ref "U16") (pin "2") (pinfunction "GND_2") (pintype "power_in"))
      (node (ref "U17") (pin "3") (pinfunction "GND_3") (pintype "passive"))
      (node (ref "U18") (pin "2") (pinfunction "GND_2") (pintype "power_in"))
    )
    (net (code "254") (name "MATENET_GND") (class "Default")
      (node (ref "C124") (pin "1") (pinfunction "1_1") (pintype "passive"))
      (node (ref "C125") (pin "1") (pinfunction "1_1") (pintype "passive"))
      (node (ref "C126") (pin "1") (pinfunction "1_1") (pintype "passive"))
      (node (ref "C127") (pin "1") (pinfunction "1_1") (pintype "passive"))
      (node (ref "J15") (pin "3") (pinfunction "SHIELD_3") (pintype "passive"))
    )
    (net (code "255") (name "MINIFAKRA_GND") (class "Default")
      (node (ref "C120") (pin "1") (pinfunction "1_1") (pintype "passive"))
      (node (ref "C121") (pin "1") (pinfunction "1_1") (pintype "passive"))
      (node (ref "C122") (pin "1") (pinfunction "1_1") (pintype "passive"))
      (node (ref "C123") (pin "1") (pinfunction "1_1") (pintype "passive"))
      (node (ref "J12") (pin "MH1") (pinfunction "MH1_MH1") (pintype "passive"))
      (node (ref "J12") (pin "MH2") (pinfunction "MH2_MH2") (pintype "passive"))
      (node (ref "J12") (pin "MH3") (pinfunction "MH3_MH3") (pintype "passive"))
      (node (ref "J12") (pin "MH4") (pinfunction "MH4_MH4") (pintype "passive"))
      (node (ref "J12") (pin "MH5") (pinfunction "MH5_MH5") (pintype "passive"))
    )
    (net (code "256") (name "Net-(D9-K-Pad1)") (class "Default")
      (node (ref "D9") (pin "1") (pinfunction "K_1") (pintype "passive"))
      (node (ref "R177") (pin "1") (pinfunction "1_1") (pintype "passive"))
    )
    (net (code "257") (name "Net-(D9-K-Pad4)") (class "Default")
      (node (ref "D9") (pin "4") (pinfunction "K_4") (pintype "passive"))
      (node (ref "R178") (pin "1") (pinfunction "1_1") (pintype "passive"))
    )
    (net (code "258") (name "Net-(F16-Pad1)") (class "Default")
      (node (ref "F16") (pin "1") (pinfunction "1_1") (pintype "passive"))
      (node (ref "J13") (pin "1") (pinfunction "1_1") (pintype "passive"))
    )
    (net (code "259") (name "Net-(F17-Pad1)") (class "Default")
      (node (ref "F17") (pin "1") (pinfunction "1_1") (pintype "passive"))
      (node (ref "J14") (pin "1") (pinfunction "1_1") (pintype "passive"))
    )
    (net (code "260") (name "Net-(J13-Pad2)") (class "Default")
      (node (ref "J13") (pin "2") (pinfunction "2_2") (pintype "passive"))
      (node (ref "R152") (pin "1") (pinfunction "1_1") (pintype "passive"))
    )
    (net (code "261") (name "Net-(J13-Pad4)") (class "Default")
      (node (ref "J13") (pin "4") (pinfunction "4_4") (pintype "passive"))
      (node (ref "R156") (pin "1") (pinfunction "1_1") (pintype "passive"))
    )
    (net (code "262") (name "Net-(J14-Pad2)") (class "Default")
      (node (ref "J14") (pin "2") (pinfunction "2_2") (pintype "passive"))
      (node (ref "R153") (pin "1") (pinfunction "1_1") (pintype "passive"))
    )
    (net (code "263") (name "Net-(J14-Pad4)") (class "Default")
      (node (ref "J14") (pin "4") (pinfunction "4_4") (pintype "passive"))
      (node (ref "R157") (pin "1") (pinfunction "1_1") (pintype "passive"))
    )
    (net (code "264") (name "Net-(Q12-G)") (class "Default")
      (node (ref "Q12") (pin "1") (pinfunction "G_1") (pintype "passive"))
      (node (ref "R159") (pin "2") (pinfunction "2_2") (pintype "passive"))
      (node (ref "R161") (pin "1") (pinfunction "1_1") (pintype "passive"))
    )
    (net (code "265") (name "Net-(U16-EN)") (class "Default")
      (node (ref "R138") (pin "1") (pinfunction "1_1") (pintype "passive"))
      (node (ref "R139") (pin "2") (pinfunction "2_2") (pintype "passive"))
      (node (ref "U16") (pin "4") (pinfunction "EN_4") (pintype "input"))
    )
    (net (code "266") (name "Net-(U17-B)") (class "Default")
      (node (ref "R147") (pin "1") (pinfunction "1_1") (pintype "passive"))
      (node (ref "R149") (pin "2") (pinfunction "2_2") (pintype "passive"))
      (node (ref "U17") (pin "1") (pinfunction "B_1") (pintype "input"))
    )
    (net (code "267") (name "Net-(U18-EN)") (class "Default")
      (node (ref "R150") (pin "1") (pinfunction "1_1") (pintype "passive"))
      (node (ref "R151") (pin "2") (pinfunction "2_2") (pintype "passive"))
      (node (ref "U18") (pin "4") (pinfunction "EN_4") (pintype "input"))
    )
    (net (code "269") (name "unconnected-(D24-IO1-Pad1)") (class "Default")
      (node (ref "D24") (pin "1") (pinfunction "IO1_1") (pintype "bidirectional+no_connect"))
    )
    (net (code "270") (name "unconnected-(D24-IO4-Pad5)") (class "Default")
      (node (ref "D24") (pin "5") (pinfunction "IO4_5") (pintype "bidirectional+no_connect"))
    )
    (net (code "271") (name "unconnected-(D24-NC-Pad6)") (class "Default")
      (node (ref "D24") (pin "6") (pinfunction "NC_6") (pintype "passive+no_connect"))
    )
    (net (code "272") (name "unconnected-(D24-NC-Pad10)") (class "Default")
      (node (ref "D24") (pin "10") (pinfunction "NC_10") (pintype "passive+no_connect"))
    )
    (net (code "273") (name "unconnected-(D30-IO1-Pad1)") (class "Default")
      (node (ref "D30") (pin "1") (pinfunction "IO1_1") (pintype "bidirectional+no_connect"))
    )
    (net (code "274") (name "unconnected-(D30-IO4-Pad5)") (class "Default")
      (node (ref "D30") (pin "5") (pinfunction "IO4_5") (pintype "bidirectional+no_connect"))
    )
    (net (code "275") (name "unconnected-(D30-NC-Pad6)") (class "Default")
      (node (ref "D30") (pin "6") (pinfunction "NC_6") (pintype "passive+no_connect"))
    )
    (net (code "276") (name "unconnected-(D30-NC-Pad10)") (class "Default")
      (node (ref "D30") (pin "10") (pinfunction "NC_10") (pintype "passive+no_connect"))
    )
    (net (code "277") (name "unconnected-(D31-IO1-Pad1)") (class "Default")
      (node (ref "D31") (pin "1") (pinfunction "IO1_1") (pintype "bidirectional+no_connect"))
    )
    (net (code "278") (name "unconnected-(D31-IO4-Pad5)") (class "Default")
      (node (ref "D31") (pin "5") (pinfunction "IO4_5") (pintype "bidirectional+no_connect"))
    )
    (net (code "279") (name "unconnected-(D31-NC-Pad6)") (class "Default")
      (node (ref "D31") (pin "6") (pinfunction "NC_6") (pintype "passive+no_connect"))
    )
    (net (code "280") (name "unconnected-(D31-NC-Pad10)") (class "Default")
      (node (ref "D31") (pin "10") (pinfunction "NC_10") (pintype "passive+no_connect"))
    )
    (net (code "281") (name "unconnected-(D32-IO2-Pad2)") (class "Default")
      (node (ref "D32") (pin "2") (pinfunction "IO2_2") (pintype "bidirectional+no_connect"))
    )
    (net (code "282") (name "unconnected-(D32-IO3-Pad4)") (class "Default")
      (node (ref "D32") (pin "4") (pinfunction "IO3_4") (pintype "bidirectional+no_connect"))
    )
    (net (code "283") (name "unconnected-(D32-IO4-Pad5)") (class "Default")
      (node (ref "D32") (pin "5") (pinfunction "IO4_5") (pintype "bidirectional+no_connect"))
    )
    (net (code "284") (name "unconnected-(D32-NC-Pad6)") (class "Default")
      (node (ref "D32") (pin "6") (pinfunction "NC_6") (pintype "passive+no_connect"))
    )
    (net (code "285") (name "unconnected-(D32-NC-Pad7)") (class "Default")
      (node (ref "D32") (pin "7") (pinfunction "NC_7") (pintype "passive+no_connect"))
    )
    (net (code "286") (name "unconnected-(D32-NC-Pad9)") (class "Default")
      (node (ref "D32") (pin "9") (pinfunction "NC_9") (pintype "passive+no_connect"))
    )
    (net (code "287") (name "unconnected-(J3-Pad7)") (class "Default")
      (node (ref "J3") (pin "7") (pinfunction "7_7") (pintype "passive"))
    )
    (net (code "288") (name "unconnected-(J3-Pad8)") (class "Default")
      (node (ref "J3") (pin "8") (pinfunction "8_8") (pintype "passive"))
    )
    (net (code "289") (name "unconnected-(J3-Pad15)") (class "Default")
      (node (ref "J3") (pin "15") (pinfunction "15_15") (pintype "passive"))
    )
    (net (code "290") (name "unconnected-(J3-Pad16)") (class "Default")
      (node (ref "J3") (pin "16") (pinfunction "16_16") (pintype "passive"))
    )
    (net (code "291") (name "unconnected-(J3-Pad17)") (class "Default")
      (node (ref "J3") (pin "17") (pinfunction "17_17") (pintype "passive"))
    )
    (net (code "292") (name "unconnected-(J3-Pad18)") (class "Default")
      (node (ref "J3") (pin "18") (pinfunction "18_18") (pintype "passive"))
    )
    (net (code "293") (name "unconnected-(J3-Pad19)") (class "Default")
      (node (ref "J3") (pin "19") (pinfunction "19_19") (pintype "passive"))
    )
    (net (code "294") (name "unconnected-(J3-Pad26)") (class "Default")
      (node (ref "J3") (pin "26") (pinfunction "26_26") (pintype "passive"))
    )
    (net (code "295") (name "unconnected-(J3-Pad29)") (class "Default")
      (node (ref "J3") (pin "29") (pinfunction "29_29") (pintype "passive"))
    )
    (net (code "296") (name "unconnected-(J3-Pad30)") (class "Default")
      (node (ref "J3") (pin "30") (pinfunction "30_30") (pintype "passive"))
    )
    (net (code "297") (name "unconnected-(J3-Pad31)") (class "Default")
      (node (ref "J3") (pin "31") (pinfunction "31_31") (pintype "passive"))
    )
    (net (code "298") (name "unconnected-(J4-UTIL-Pad14)") (class "Default")
      (node (ref "J4") (pin "14") (pinfunction "UTIL_14") (pintype "bidirectional+no_connect"))
    )
    (net (code "299") (name "unconnected-(J6-UTIL-Pad14)") (class "Default")
      (node (ref "J6") (pin "14") (pinfunction "UTIL_14") (pintype "bidirectional+no_connect"))
    )
    (net (code "300") (name "unconnected-(J17-D+_B-PadB6)") (class "Default")
      (node (ref "J17") (pin "B6") (pinfunction "D+_B_B6") (pintype "bidirectional+no_connect"))
    )
    (net (code "301") (name "unconnected-(J17-D-_B-PadB7)") (class "Default")
      (node (ref "J17") (pin "B7") (pinfunction "D-_B_B7") (pintype "bidirectional+no_connect"))
    )
    (net (code "302") (name "unconnected-(J17-SBU1-PadA8)") (class "Default")
      (node (ref "J17") (pin "A8") (pinfunction "SBU1_A8") (pintype "bidirectional+no_connect"))
    )
    (net (code "303") (name "unconnected-(J17-SBU2-PadB8)") (class "Default")
      (node (ref "J17") (pin "B8") (pinfunction "SBU2_B8") (pintype "bidirectional+no_connect"))
    )
    (net (code "304") (name "unconnected-(J17-VBUS-PadA4_B9)") (class "Default")
      (node (ref "J17") (pin "A4_B9") (pinfunction "VBUS_A4_B9") (pintype "power_in+no_connect"))
    )
    (net (code "305") (name "unconnected-(J17-VBUS-PadB4_A9)") (class "Default")
      (node (ref "J17") (pin "B4_A9") (pinfunction "VBUS_B4_A9") (pintype "power_in+no_connect"))
    )
    (net (code "306") (name "unconnected-(U16-nFLG-Pad3)") (class "Default")
      (node (ref "U16") (pin "3") (pinfunction "nFLG_3") (pintype "output+no_connect"))
    )
    (net (code "307") (name "unconnected-(U18-nFLG-Pad3)") (class "Default")
      (node (ref "U18") (pin "3") (pinfunction "nFLG_3") (pintype "output+no_connect"))
    )
  )
)
